# 612_jetracer_328_212.net
KiCad netlist of a schematic drawn in EAGLE
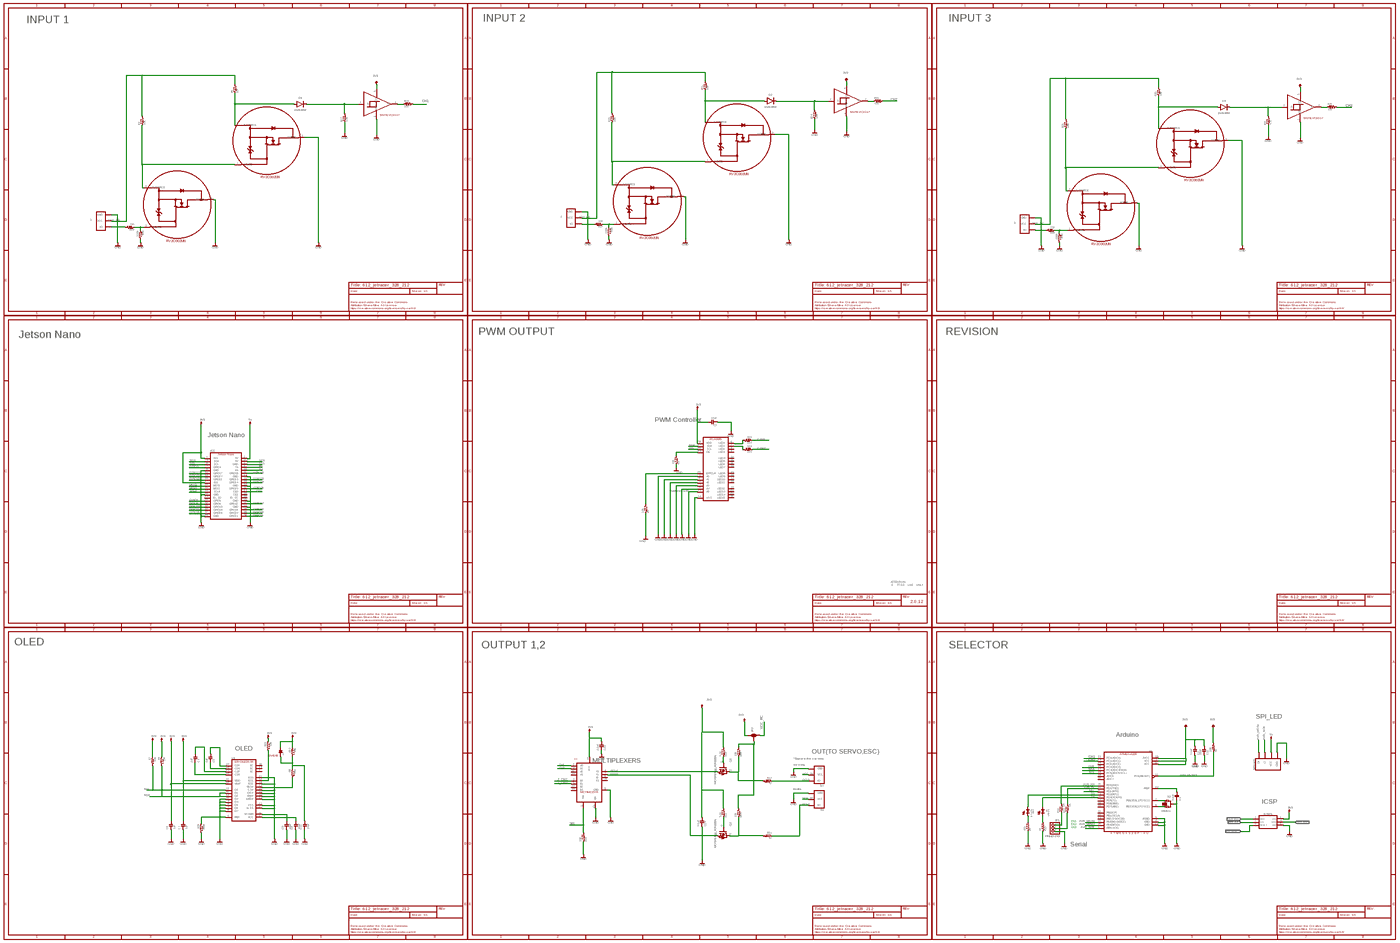
[diagram p0: schematic, sheet 1, overview]
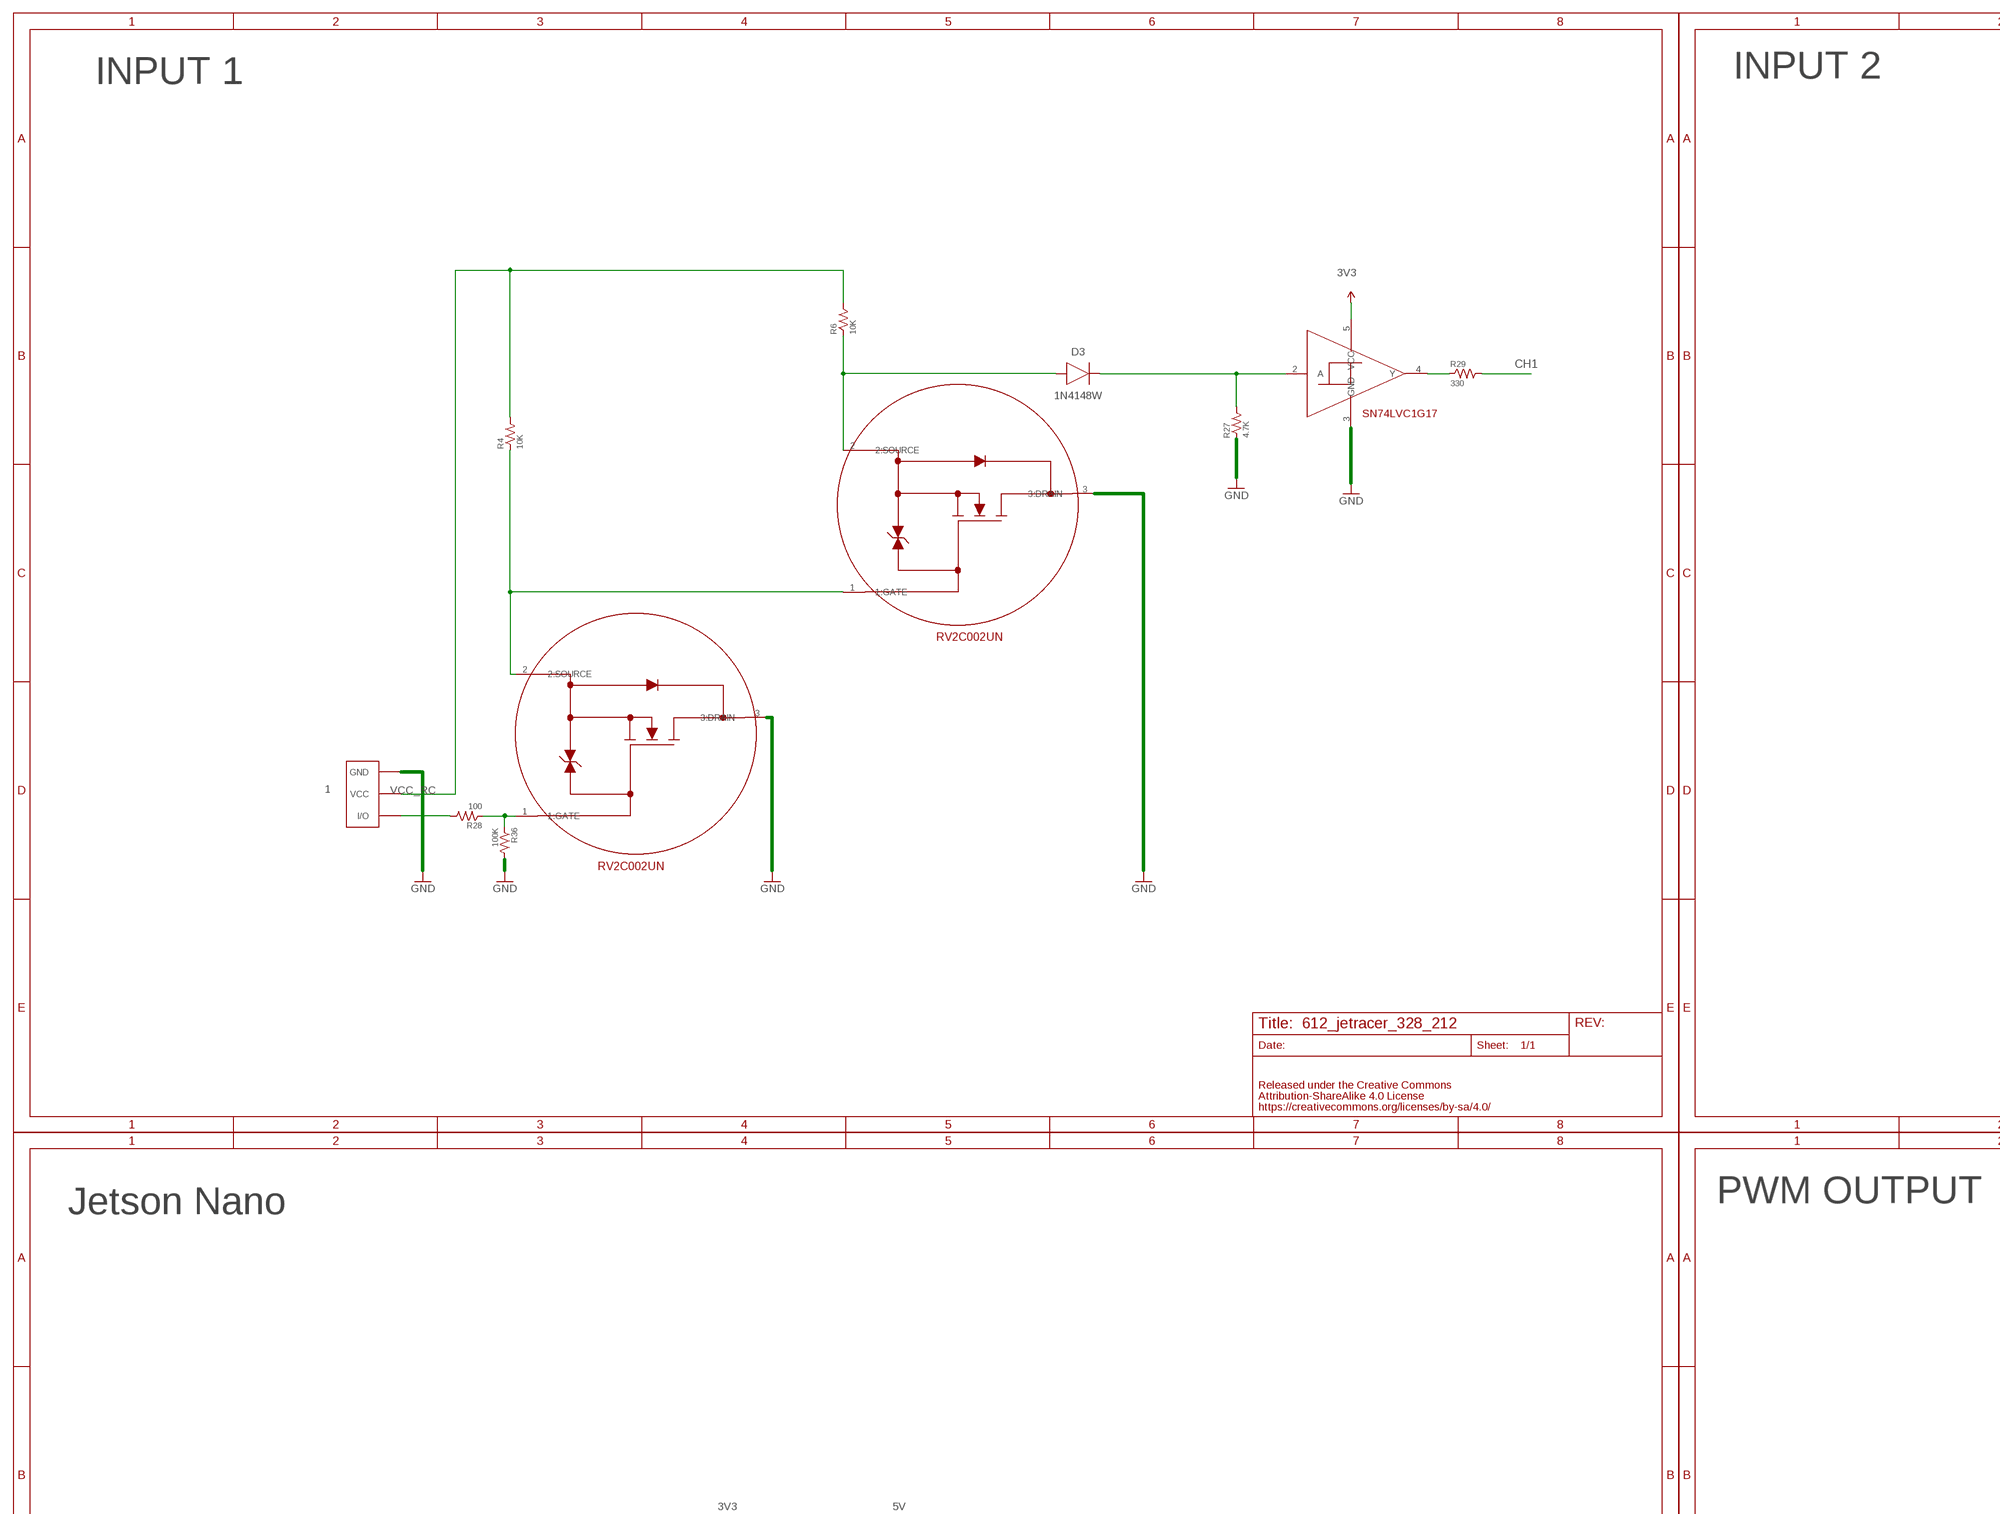
[diagram p1: schematic, sheet 1, part 1 of 6]
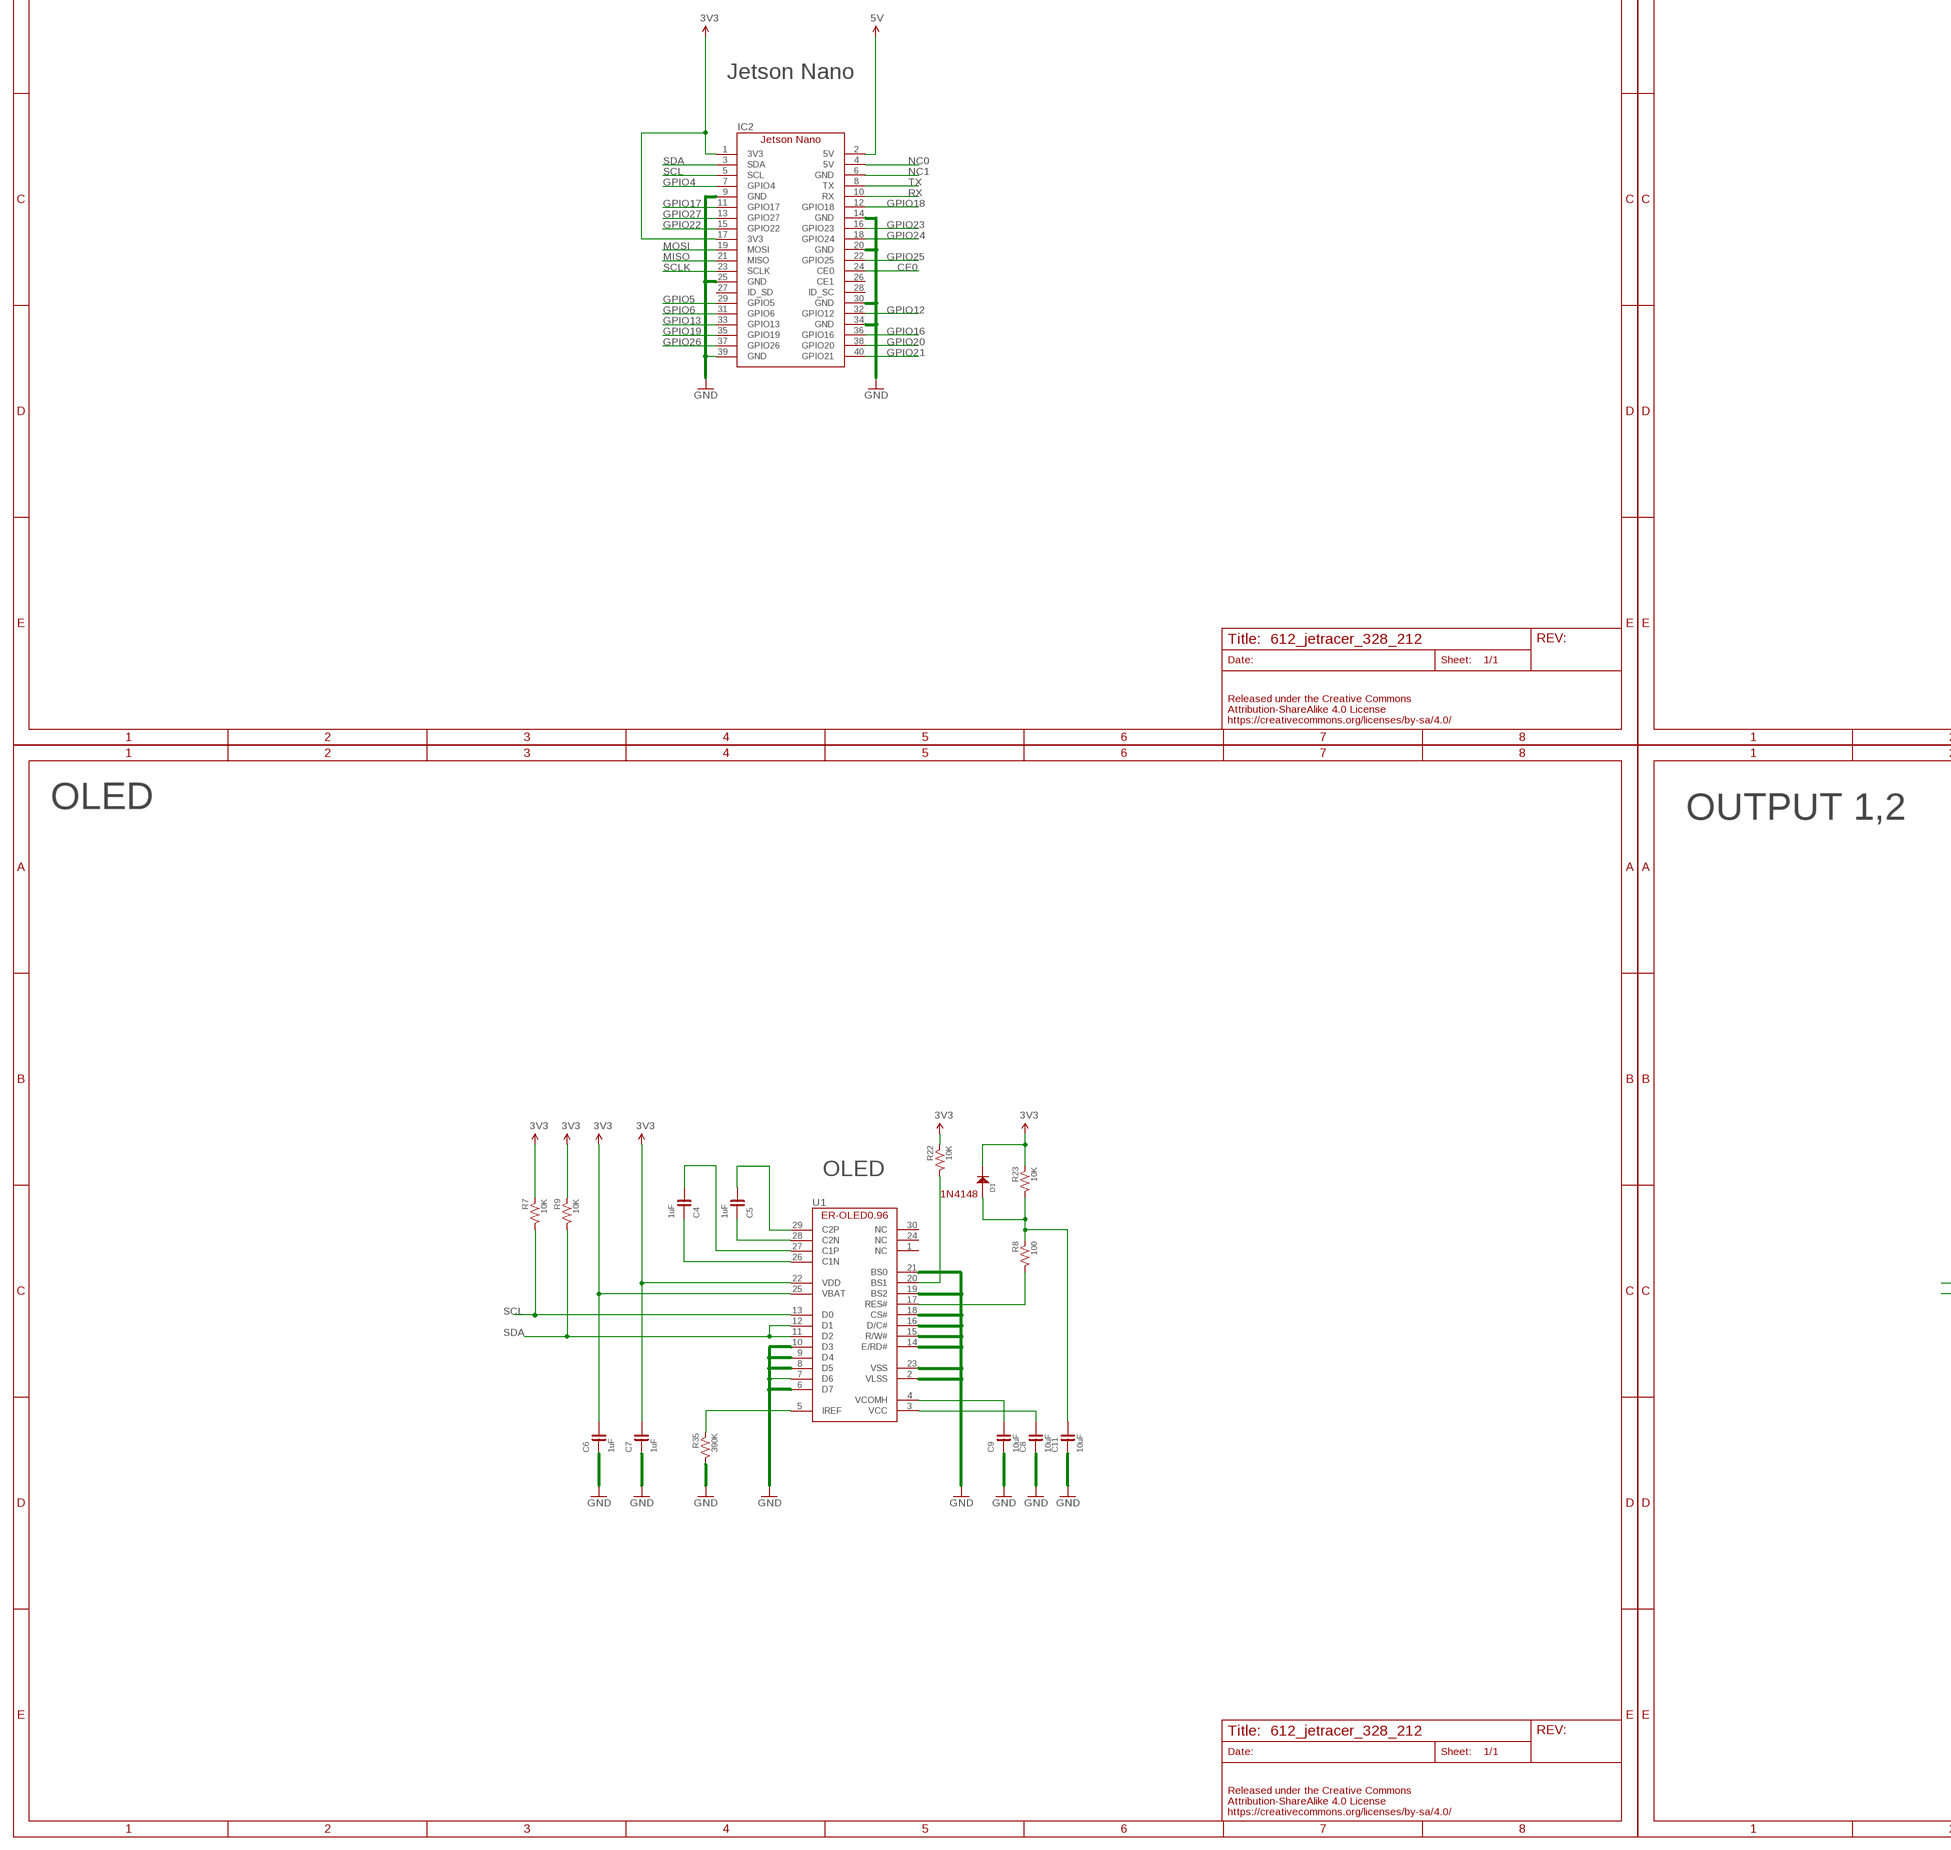
[diagram p2: schematic, sheet 1, part 2 of 6]
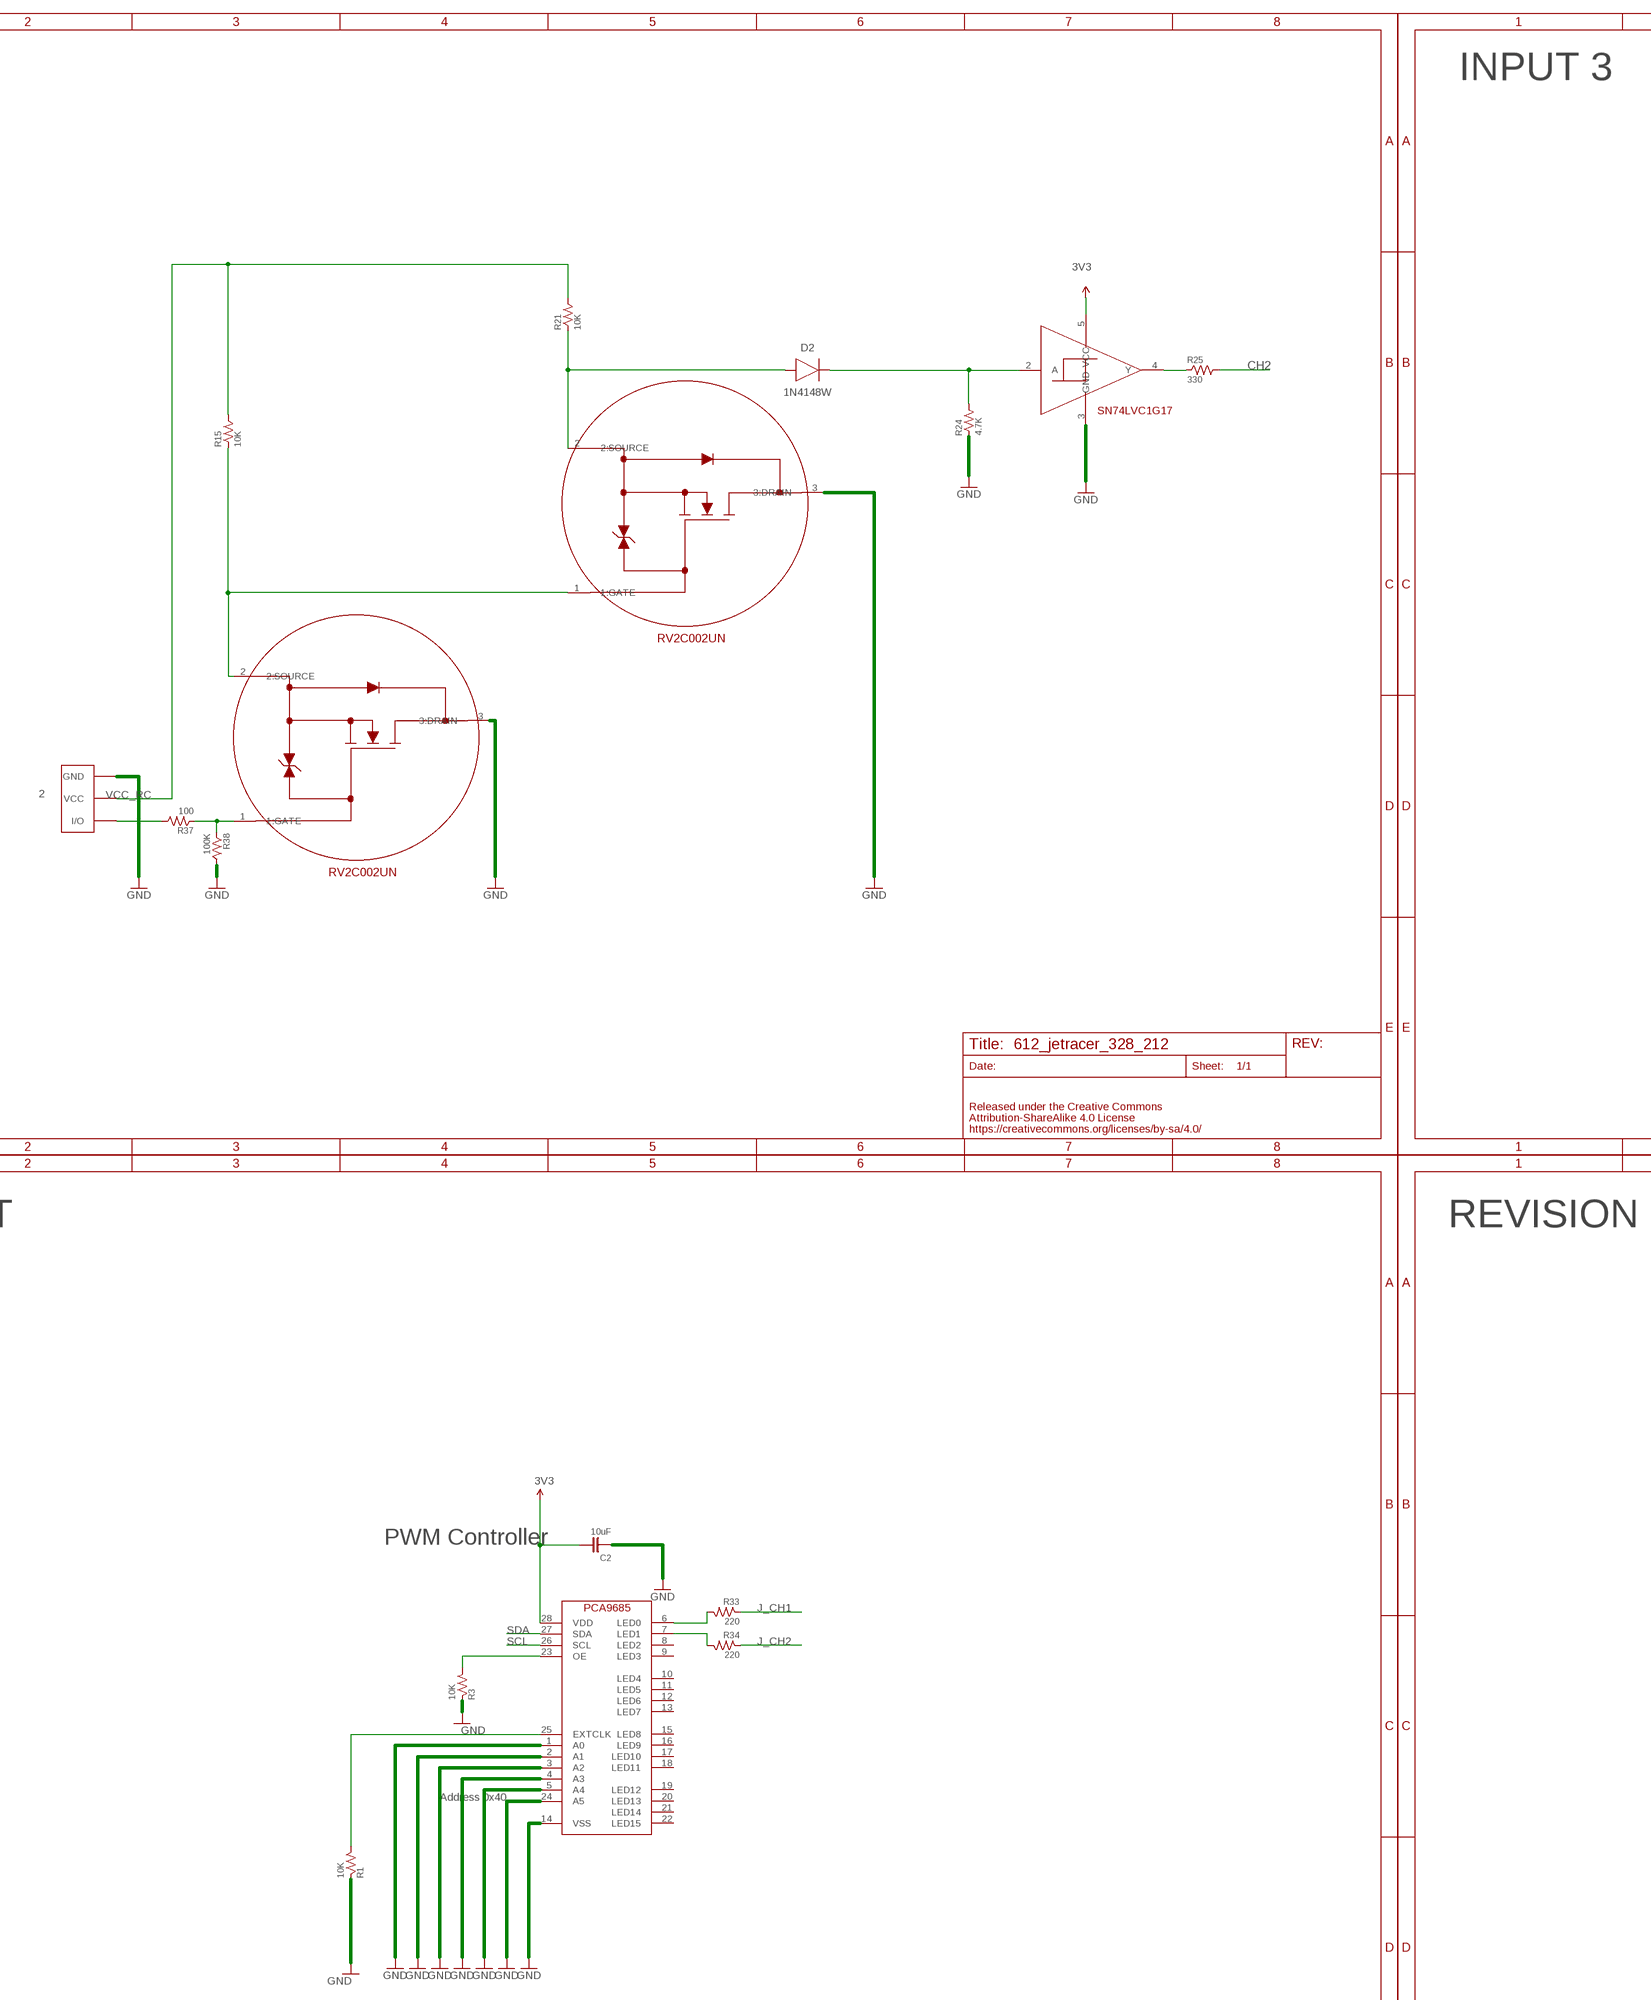
[diagram p3: schematic, sheet 1, part 3 of 6]
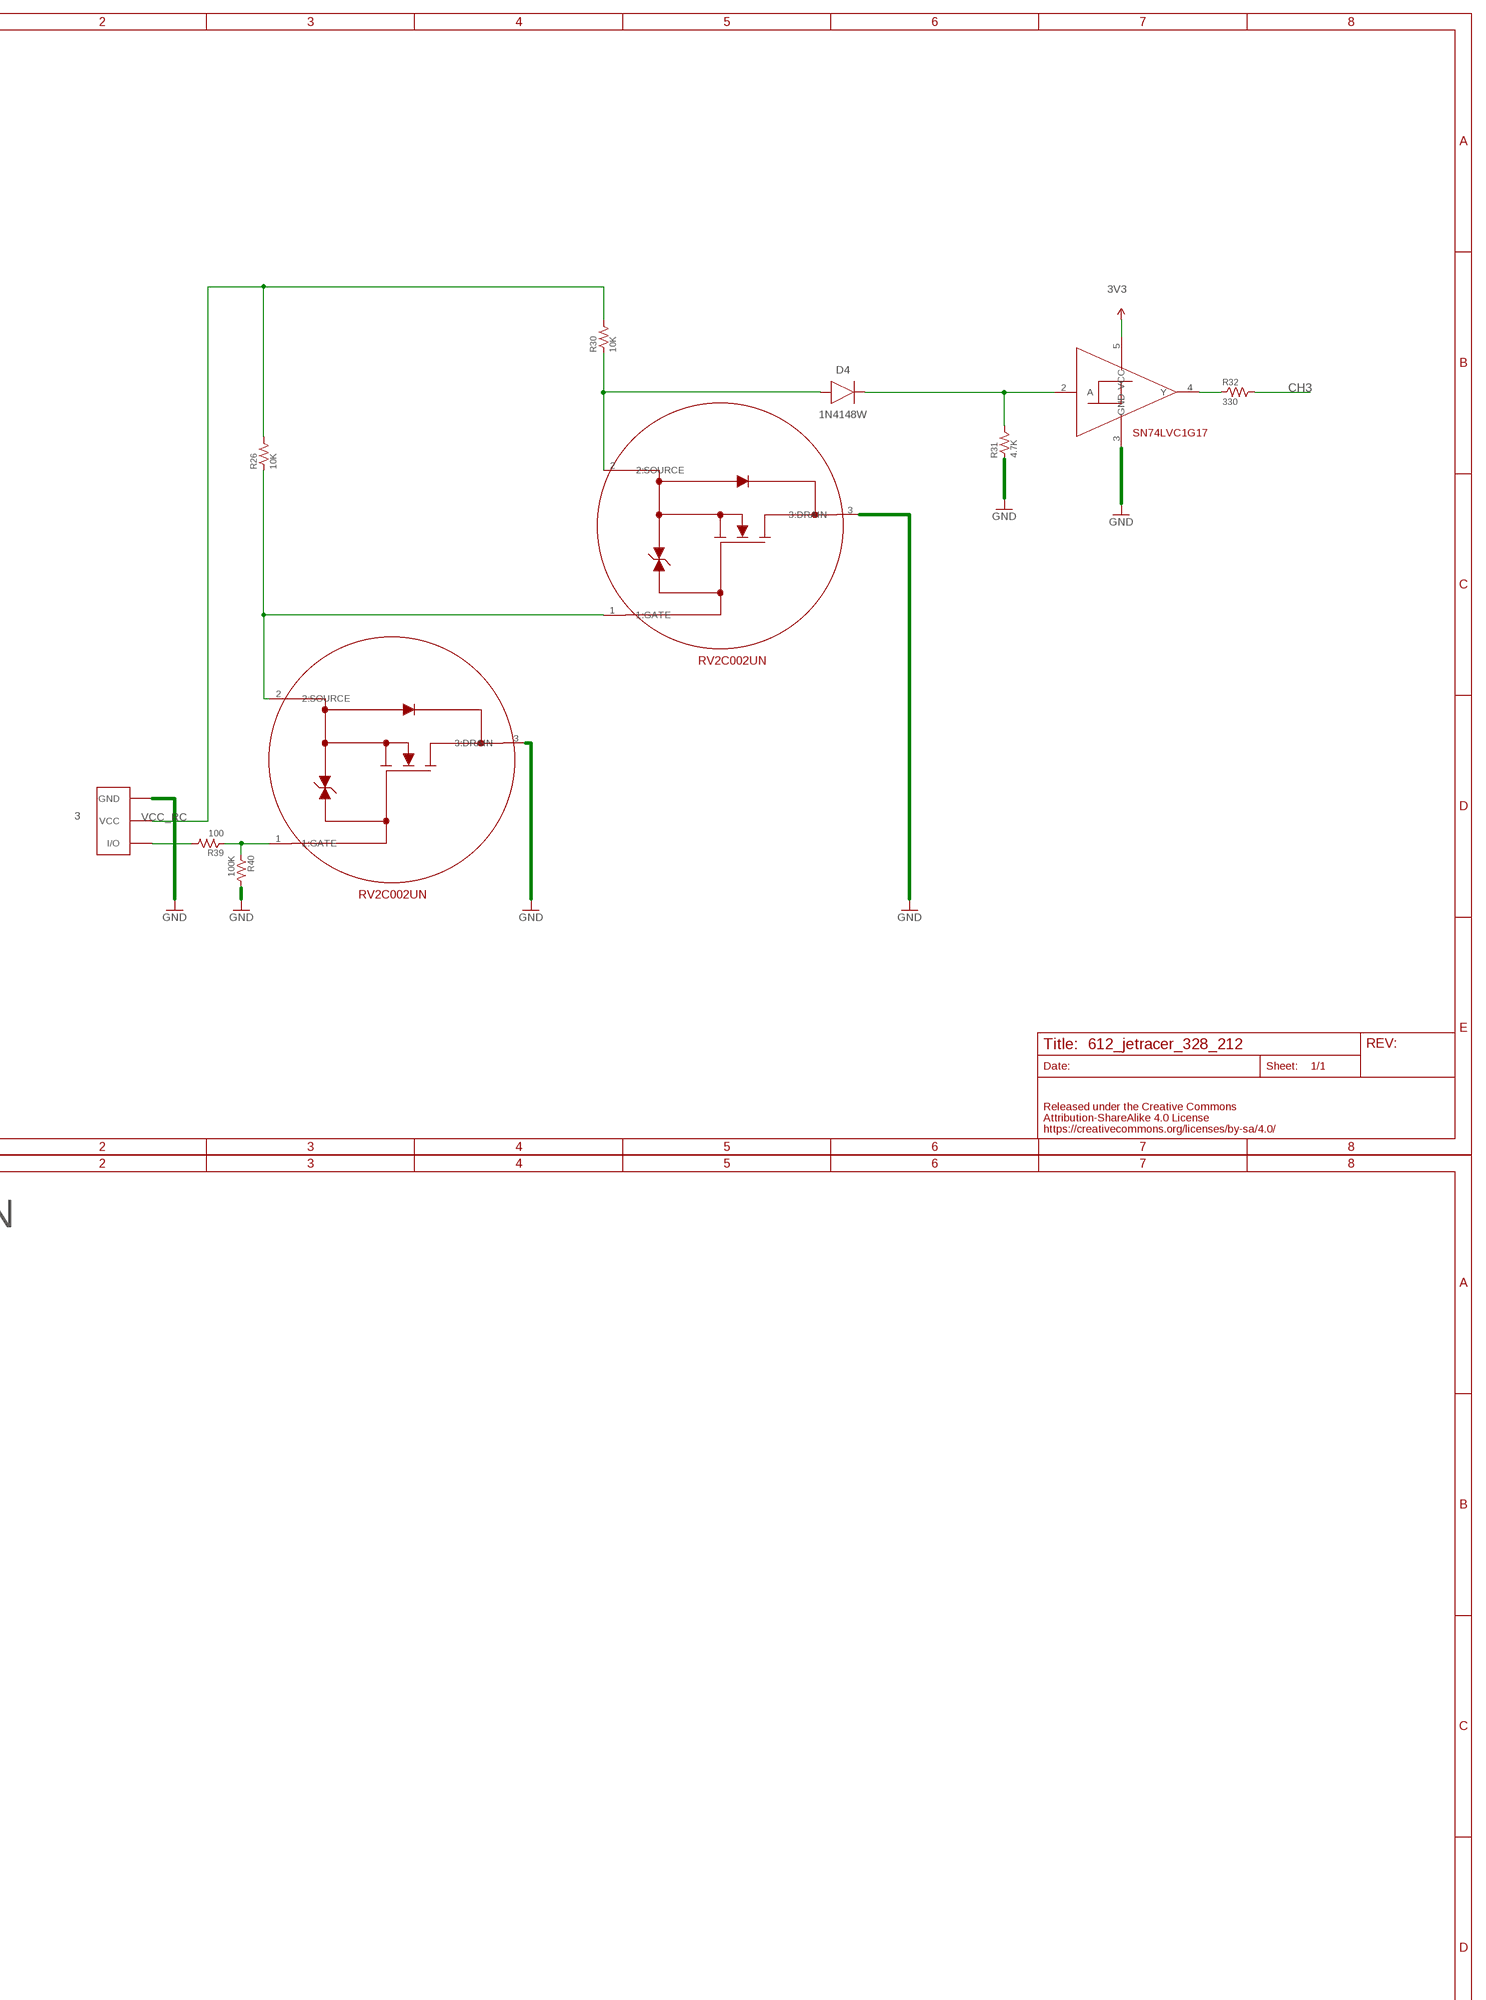
[diagram p4: schematic, sheet 1, part 4 of 6]
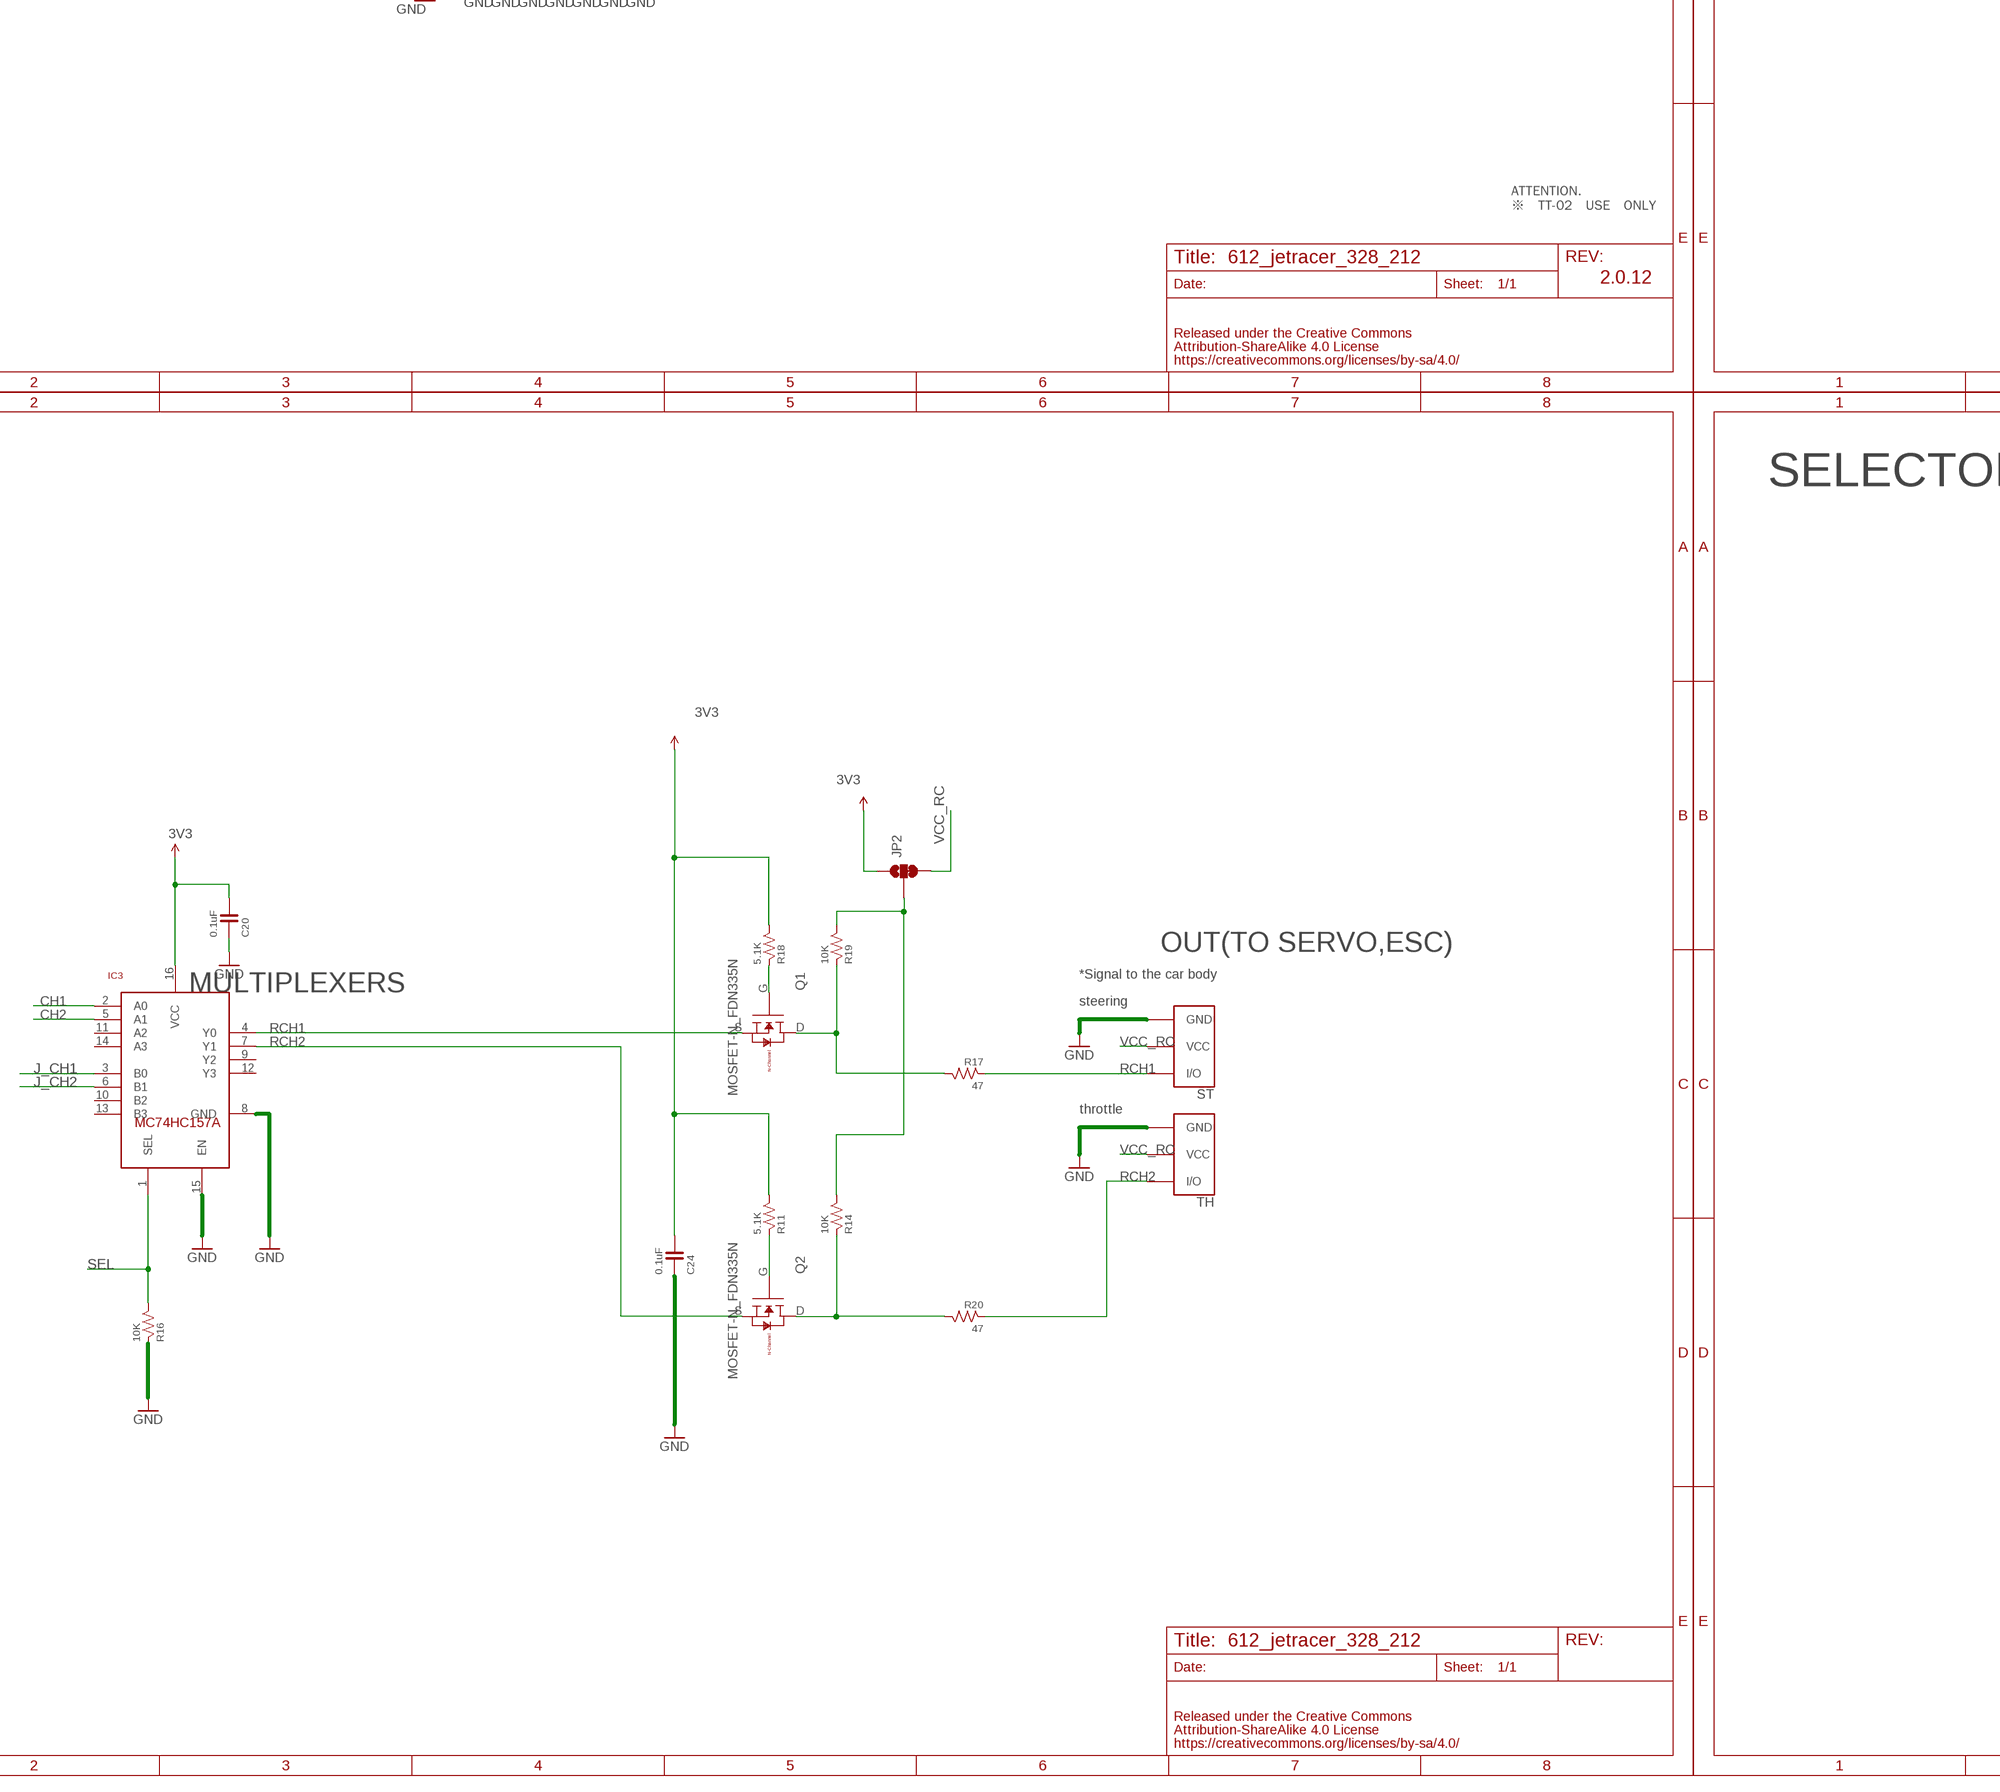
[diagram p5: schematic, sheet 1, part 5 of 6]
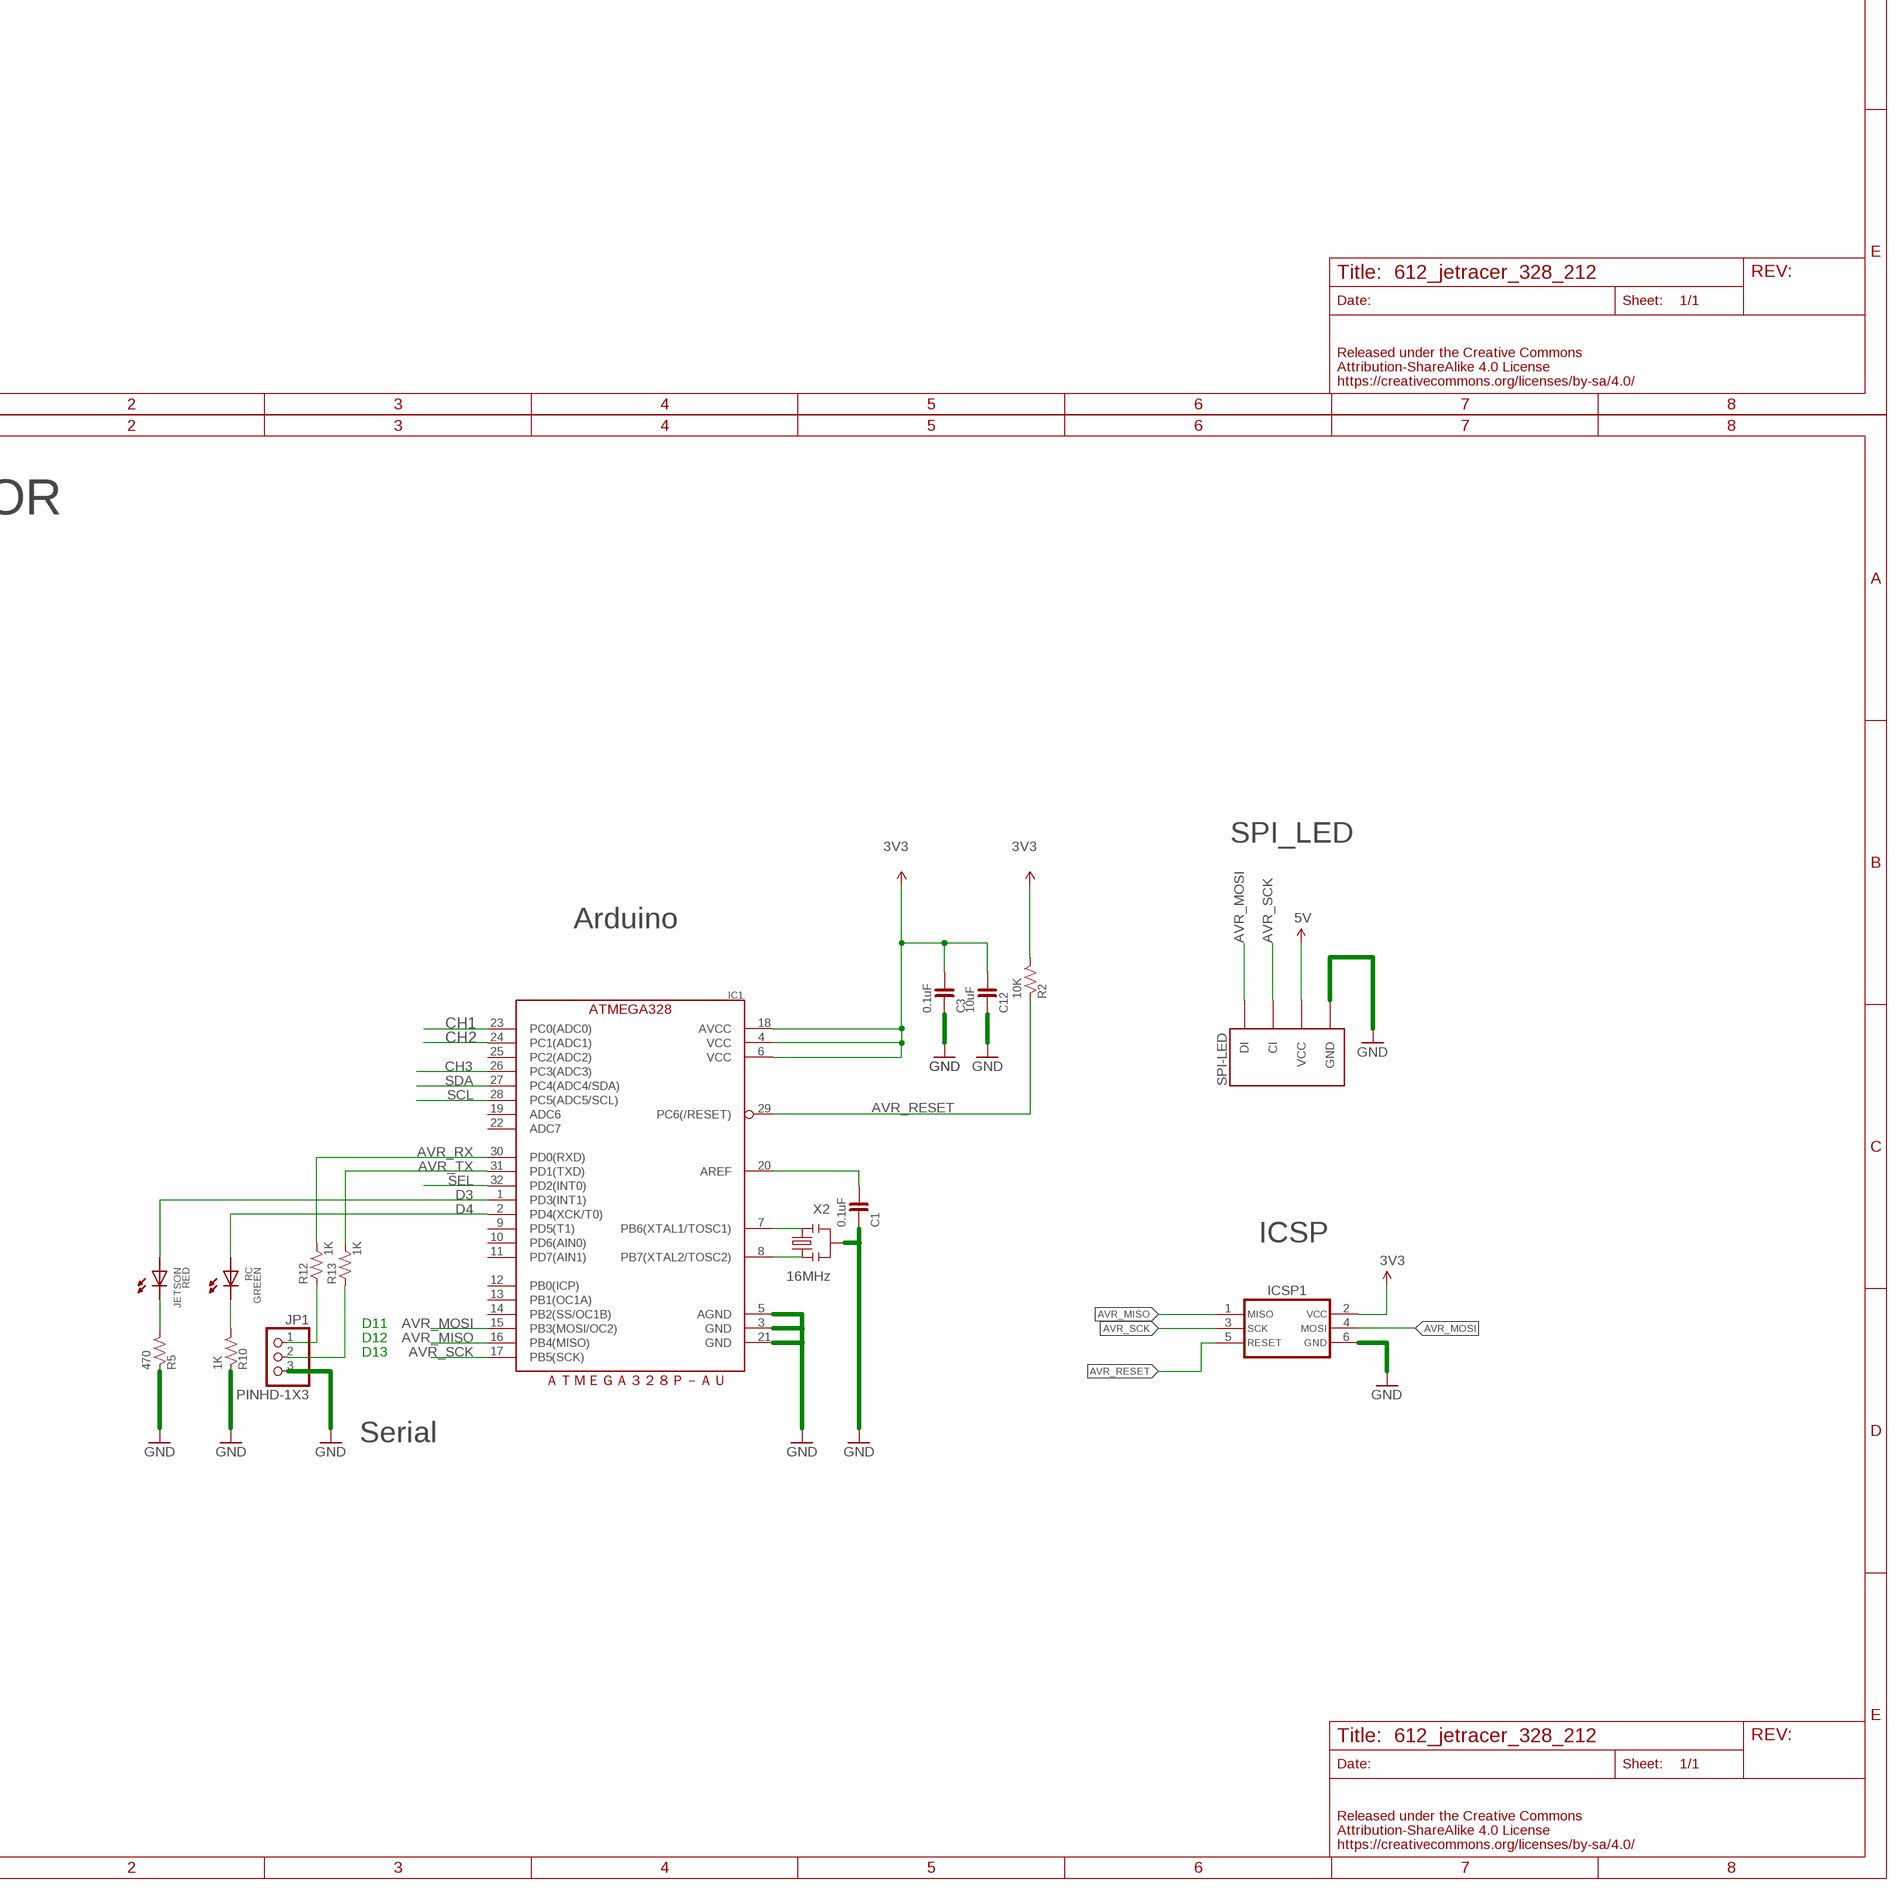
[diagram p6: schematic, sheet 1, part 6 of 6]

(export (version "E")
  (design (tool "Eeschema 10.0.6"))
  (components
    (comp (ref "1")
      (value "FABO_BRICK_3PIN-HEADER")
      (footprint "eagle-import:FABO_BRICK_3PIN_HEADER")
      (libsource (lib "eagle-import") (part "FABO_BRICK_3PIN-HEADER"))
    )
    (comp (ref "2")
      (value "FABO_BRICK_3PIN-HEADER")
      (footprint "eagle-import:FABO_BRICK_3PIN_HEADER")
      (libsource (lib "eagle-import") (part "FABO_BRICK_3PIN-HEADER"))
    )
    (comp (ref "3")
      (value "FABO_BRICK_3PIN-HEADER")
      (footprint "eagle-import:FABO_BRICK_3PIN_HEADER")
      (libsource (lib "eagle-import") (part "FABO_BRICK_3PIN-HEADER"))
    )
    (comp (ref "C1")
      (value "0.1uF")
      (footprint "eagle-import:0603")
      (libsource (lib "eagle-import") (part "CAPACITOR-0603"))
    )
    (comp (ref "C2")
      (value "10uF")
      (footprint "eagle-import:0603")
      (libsource (lib "eagle-import") (part "CAPACITOR-0603"))
    )
    (comp (ref "C3")
      (value "0.1uF")
      (footprint "eagle-import:0603")
      (libsource (lib "eagle-import") (part "CAPACITOR-0603"))
    )
    (comp (ref "C4")
      (value "1uF")
      (footprint "eagle-import:0603")
      (libsource (lib "eagle-import") (part "CAPACITOR-0603"))
    )
    (comp (ref "C5")
      (value "1uF")
      (footprint "eagle-import:0603")
      (libsource (lib "eagle-import") (part "CAPACITOR-0603"))
    )
    (comp (ref "C6")
      (value "1uF")
      (footprint "eagle-import:0603")
      (libsource (lib "eagle-import") (part "CAPACITOR-0603"))
    )
    (comp (ref "C7")
      (value "1uF")
      (footprint "eagle-import:0603")
      (libsource (lib "eagle-import") (part "CAPACITOR-0603"))
    )
    (comp (ref "C8")
      (value "10uF")
      (footprint "eagle-import:0603")
      (libsource (lib "eagle-import") (part "CAPACITOR-0603"))
    )
    (comp (ref "C9")
      (value "10uF")
      (footprint "eagle-import:0603")
      (libsource (lib "eagle-import") (part "CAPACITOR-0603"))
    )
    (comp (ref "C11")
      (value "10uF")
      (footprint "eagle-import:0603")
      (libsource (lib "eagle-import") (part "CAPACITOR-0603"))
    )
    (comp (ref "C12")
      (value "10uF")
      (footprint "eagle-import:0603")
      (libsource (lib "eagle-import") (part "CAPACITOR-0603"))
    )
    (comp (ref "C20")
      (value "0.1uF")
      (footprint "eagle-import:0603")
      (libsource (lib "eagle-import") (part "CAPACITOR-0603"))
    )
    (comp (ref "C24")
      (value "0.1uF")
      (footprint "eagle-import:0603")
      (fields (field (name "SPICEPREFIX") "C"))
      (libsource (lib "eagle-import") (part "CAPACITOR-0603"))
    )
    (comp (ref "D1")
      (value "1N4148")
      (footprint "eagle-import:1N4148W")
      (libsource (lib "eagle-import") (part "1N4148"))
    )
    (comp (ref "D2")
      (value "1N4148W")
      (footprint "eagle-import:SOD3715X135")
      (fields (field (name "MANUFACTURER") "Diodes Incorporated"))
      (libsource (lib "eagle-import") (part "DIODE__SOD123G1N4148W-7-F"))
    )
    (comp (ref "D3")
      (value "1N4148W")
      (footprint "eagle-import:SOD3715X135")
      (fields (field (name "MANUFACTURER") "Diodes Incorporated"))
      (libsource (lib "eagle-import") (part "DIODE__SOD123G1N4148W-7-F"))
    )
    (comp (ref "D4")
      (value "1N4148W")
      (footprint "eagle-import:SOD3715X135")
      (fields (field (name "MANUFACTURER") "Diodes Incorporated"))
      (libsource (lib "eagle-import") (part "DIODE__SOD123G1N4148W-7-F"))
    )
    (comp (ref "IC1")
      (value "ATMEGA328P-AU")
      (footprint "eagle-import:TQFP-32")
      (libsource (lib "eagle-import") (part "ATMEGA328P-AU"))
    )
    (comp (ref "IC2")
      (value "JETSON_NANO_NOBORDER")
      (footprint "eagle-import:JETSON_NANO_NOBOARDER")
      (libsource (lib "eagle-import") (part "JETSON_NANO_NOBORDER"))
    )
    (comp (ref "IC3")
      (value "MULTIPLEXERSMC74HC157A")
      (footprint "eagle-import:TSSOP-16")
      (libsource (lib "eagle-import") (part "MULTIPLEXERSMC74HC157A"))
    )
    (comp (ref "IC4")
      (value "PCA9685")
      (footprint "eagle-import:PCA9685")
      (libsource (lib "eagle-import") (part "PCA9685"))
    )
    (comp (ref "ICSP1")
      (value "ICSP_AVR-TC_NOHOLE")
      (footprint "eagle-import:TC2030")
      (libsource (lib "eagle-import") (part "ICSP_AVR-TC_NOHOLE"))
    )
    (comp (ref "JETSON")
      (value "GREEN")
      (footprint "eagle-import:0603")
      (libsource (lib "eagle-import") (part "LED-0603"))
    )
    (comp (ref "JP1")
      (value "PINHD-1X3")
      (footprint "eagle-import:1X03")
      (libsource (lib "eagle-import") (part "PINHD-1X3"))
    )
    (comp (ref "JP2")
      (value "JUMPER-SMT_3_1-NC_TRACE_SILK")
      (footprint "eagle-import:SMT-JUMPER_3_1-NC_TRACE_SILK")
      (libsource (lib "eagle-import") (part "JUMPER-SMT_3_1-NC_TRACE_SILK"))
    )
    (comp (ref "Q1")
      (value "MOSFET-N_FDN335N")
      (footprint "eagle-import:SUPERSOT-3")
      (libsource (lib "eagle-import") (part "MOSFET-N_FDN335N"))
    )
    (comp (ref "Q2")
      (value "MOSFET-N_FDN335N")
      (footprint "eagle-import:SUPERSOT-3")
      (libsource (lib "eagle-import") (part "MOSFET-N_FDN335N"))
    )
    (comp (ref "R1")
      (value "10K")
      (footprint "eagle-import:0603")
      (libsource (lib "eagle-import") (part "RESISTOR-0603"))
    )
    (comp (ref "R2")
      (value "10K")
      (footprint "eagle-import:0603")
      (libsource (lib "eagle-import") (part "RESISTOR-0603"))
    )
    (comp (ref "R3")
      (value "10K")
      (footprint "eagle-import:0603")
      (libsource (lib "eagle-import") (part "RESISTOR-0603"))
    )
    (comp (ref "R4")
      (value "10K")
      (footprint "eagle-import:0603")
      (libsource (lib "eagle-import") (part "RESISTOR-0603"))
    )
    (comp (ref "R5")
      (value "470")
      (footprint "eagle-import:0603")
      (libsource (lib "eagle-import") (part "RESISTOR-0603"))
    )
    (comp (ref "R6")
      (value "10K")
      (footprint "eagle-import:0603")
      (libsource (lib "eagle-import") (part "RESISTOR-0603"))
    )
    (comp (ref "R7")
      (value "10K")
      (footprint "eagle-import:0603")
      (libsource (lib "eagle-import") (part "RESISTOR-0603"))
    )
    (comp (ref "R8")
      (value "100")
      (footprint "eagle-import:0603")
      (libsource (lib "eagle-import") (part "RESISTOR-0603"))
    )
    (comp (ref "R9")
      (value "10K")
      (footprint "eagle-import:0603")
      (libsource (lib "eagle-import") (part "RESISTOR-0603"))
    )
    (comp (ref "R10")
      (value "1K")
      (footprint "eagle-import:0603")
      (libsource (lib "eagle-import") (part "RESISTOR-0603"))
    )
    (comp (ref "R11")
      (value "5.1K")
      (footprint "eagle-import:0603")
      (libsource (lib "eagle-import") (part "RESISTOR-0603"))
    )
    (comp (ref "R12")
      (value "1K")
      (footprint "eagle-import:0603")
      (libsource (lib "eagle-import") (part "RESISTOR-0603"))
    )
    (comp (ref "R13")
      (value "1K")
      (footprint "eagle-import:0603")
      (libsource (lib "eagle-import") (part "RESISTOR-0603"))
    )
    (comp (ref "R14")
      (value "10K")
      (footprint "eagle-import:0603")
      (libsource (lib "eagle-import") (part "RESISTOR-0603"))
    )
    (comp (ref "R15")
      (value "10K")
      (footprint "eagle-import:0603")
      (libsource (lib "eagle-import") (part "RESISTOR-0603"))
    )
    (comp (ref "R16")
      (value "10K")
      (footprint "eagle-import:0603")
      (libsource (lib "eagle-import") (part "RESISTOR-0603"))
    )
    (comp (ref "R17")
      (value "47")
      (footprint "eagle-import:0603")
      (libsource (lib "eagle-import") (part "RESISTOR-0603"))
    )
    (comp (ref "R18")
      (value "5.1K")
      (footprint "eagle-import:0603")
      (libsource (lib "eagle-import") (part "RESISTOR-0603"))
    )
    (comp (ref "R19")
      (value "10K")
      (footprint "eagle-import:0603")
      (libsource (lib "eagle-import") (part "RESISTOR-0603"))
    )
    (comp (ref "R20")
      (value "47")
      (footprint "eagle-import:0603")
      (libsource (lib "eagle-import") (part "RESISTOR-0603"))
    )
    (comp (ref "R21")
      (value "10K")
      (footprint "eagle-import:0603")
      (libsource (lib "eagle-import") (part "RESISTOR-0603"))
    )
    (comp (ref "R22")
      (value "10K")
      (footprint "eagle-import:0603")
      (libsource (lib "eagle-import") (part "RESISTOR-0603"))
    )
    (comp (ref "R23")
      (value "10K")
      (footprint "eagle-import:0603")
      (libsource (lib "eagle-import") (part "RESISTOR-0603"))
    )
    (comp (ref "R24")
      (value "4.7K")
      (footprint "eagle-import:0603")
      (libsource (lib "eagle-import") (part "RESISTOR-0603"))
    )
    (comp (ref "R25")
      (value "330")
      (footprint "eagle-import:0603")
      (libsource (lib "eagle-import") (part "RESISTOR-0603"))
    )
    (comp (ref "R26")
      (value "10K")
      (footprint "eagle-import:0603")
      (libsource (lib "eagle-import") (part "RESISTOR-0603"))
    )
    (comp (ref "R27")
      (value "4.7K")
      (footprint "eagle-import:0603")
      (libsource (lib "eagle-import") (part "RESISTOR-0603"))
    )
    (comp (ref "R28")
      (value "100")
      (footprint "eagle-import:0603")
      (libsource (lib "eagle-import") (part "RESISTOR-0603"))
    )
    (comp (ref "R29")
      (value "330")
      (footprint "eagle-import:0603")
      (libsource (lib "eagle-import") (part "RESISTOR-0603"))
    )
    (comp (ref "R30")
      (value "10K")
      (footprint "eagle-import:0603")
      (libsource (lib "eagle-import") (part "RESISTOR-0603"))
    )
    (comp (ref "R31")
      (value "4.7K")
      (footprint "eagle-import:0603")
      (libsource (lib "eagle-import") (part "RESISTOR-0603"))
    )
    (comp (ref "R32")
      (value "330")
      (footprint "eagle-import:0603")
      (libsource (lib "eagle-import") (part "RESISTOR-0603"))
    )
    (comp (ref "R33")
      (value "220")
      (footprint "eagle-import:0603")
      (libsource (lib "eagle-import") (part "RESISTOR-0603"))
    )
    (comp (ref "R34")
      (value "220")
      (footprint "eagle-import:0603")
      (libsource (lib "eagle-import") (part "RESISTOR-0603"))
    )
    (comp (ref "R35")
      (value "390K")
      (footprint "eagle-import:0603")
      (libsource (lib "eagle-import") (part "RESISTOR-0603"))
    )
    (comp (ref "R36")
      (value "100K")
      (footprint "eagle-import:0603")
      (libsource (lib "eagle-import") (part "RESISTOR-0603"))
    )
    (comp (ref "R37")
      (value "100")
      (footprint "eagle-import:0603")
      (libsource (lib "eagle-import") (part "RESISTOR-0603"))
    )
    (comp (ref "R38")
      (value "100K")
      (footprint "eagle-import:0603")
      (libsource (lib "eagle-import") (part "RESISTOR-0603"))
    )
    (comp (ref "R39")
      (value "100")
      (footprint "eagle-import:0603")
      (libsource (lib "eagle-import") (part "RESISTOR-0603"))
    )
    (comp (ref "R40")
      (value "100K")
      (footprint "eagle-import:0603")
      (libsource (lib "eagle-import") (part "RESISTOR-0603"))
    )
    (comp (ref "RC")
      (value "RED")
      (footprint "eagle-import:0603")
      (libsource (lib "eagle-import") (part "LED-0603"))
    )
    (comp (ref "SPI-LED")
      (value "FABO-SPI-LED-B04B")
      (footprint "eagle-import:SPI-B04B-PASK-1")
      (libsource (lib "eagle-import") (part "FABO-SPI-LED-B04B"))
    )
    (comp (ref "ST")
      (value "FABO_BRICK_3PIN-HEADER")
      (footprint "eagle-import:FABO_BRICK_3PIN_HEADER")
      (libsource (lib "eagle-import") (part "FABO_BRICK_3PIN-HEADER"))
    )
    (comp (ref "TH")
      (value "FABO_BRICK_3PIN-HEADER")
      (footprint "eagle-import:FABO_BRICK_3PIN_HEADER")
      (libsource (lib "eagle-import") (part "FABO_BRICK_3PIN-HEADER"))
    )
    (comp (ref "U$4")
      (value "RV2C002UN")
      (footprint "eagle-import:DFN1006-3")
      (libsource (lib "eagle-import") (part "RV2C002UN"))
    )
    (comp (ref "U$5")
      (value "RV2C002UN")
      (footprint "eagle-import:DFN1006-3")
      (libsource (lib "eagle-import") (part "RV2C002UN"))
    )
    (comp (ref "U$8")
      (value "RV2C002UN")
      (footprint "eagle-import:DFN1006-3")
      (libsource (lib "eagle-import") (part "RV2C002UN"))
    )
    (comp (ref "U$9")
      (value "RV2C002UN")
      (footprint "eagle-import:DFN1006-3")
      (libsource (lib "eagle-import") (part "RV2C002UN"))
    )
    (comp (ref "U$14")
      (value "SN74LVC1G17")
      (footprint "eagle-import:SOT-23")
      (libsource (lib "eagle-import") (part "SN74LVC1G17"))
    )
    (comp (ref "U$20")
      (value "SN74LVC1G17")
      (footprint "eagle-import:SOT-23")
      (libsource (lib "eagle-import") (part "SN74LVC1G17"))
    )
    (comp (ref "U$21")
      (value "RV2C002UN")
      (footprint "eagle-import:DFN1006-3")
      (libsource (lib "eagle-import") (part "RV2C002UN"))
    )
    (comp (ref "U$22")
      (value "RV2C002UN")
      (footprint "eagle-import:DFN1006-3")
      (libsource (lib "eagle-import") (part "RV2C002UN"))
    )
    (comp (ref "U$23")
      (value "SN74LVC1G17")
      (footprint "eagle-import:SOT-23")
      (libsource (lib "eagle-import") (part "SN74LVC1G17"))
    )
    (comp (ref "U1")
      (value "ER-OLED0.96-1ER-CON30HT-1")
      (footprint "eagle-import:ER-CON30HT-1")
      (libsource (lib "eagle-import") (part "ER-OLED0.96-1ER-CON30HT-1"))
    )
    (comp (ref "X2")
      (value "16MHz")
      (footprint "eagle-import:CSTNE_V_C")
      (libsource (lib "eagle-import") (part "RESONATOR"))
    )
  )
  (nets
    (net (code "1") (name "/AVR_RX") (class "Default")
      (node (ref "IC1") (pin "30") (pinfunction "PD0(RXD)_30") (pintype "bidirectional"))
      (node (ref "R12") (pin "2") (pinfunction "2_2") (pintype "bidirectional"))
    )
    (net (code "2") (name "/AVR_TX") (class "Default")
      (node (ref "IC1") (pin "31") (pinfunction "PD1(TXD)_31") (pintype "bidirectional"))
      (node (ref "R13") (pin "2") (pinfunction "2_2") (pintype "bidirectional"))
    )
    (net (code "3") (name "/CE0") (class "Default")
      (node (ref "IC2") (pin "24") (pinfunction "CE0_24") (pintype "bidirectional"))
    )
    (net (code "4") (name "/CH1") (class "Default")
      (node (ref "IC1") (pin "23") (pinfunction "PC0(ADC0)_23") (pintype "bidirectional"))
      (node (ref "IC3") (pin "2") (pinfunction "A0_2") (pintype "bidirectional"))
      (node (ref "R29") (pin "2") (pinfunction "2_2") (pintype "bidirectional"))
    )
    (net (code "5") (name "/CH2") (class "Default")
      (node (ref "IC1") (pin "24") (pinfunction "PC1(ADC1)_24") (pintype "bidirectional"))
      (node (ref "IC3") (pin "5") (pinfunction "A1_5") (pintype "bidirectional"))
      (node (ref "R25") (pin "2") (pinfunction "2_2") (pintype "bidirectional"))
    )
    (net (code "6") (name "/CH3") (class "Default")
      (node (ref "IC1") (pin "26") (pinfunction "PC3(ADC3)_26") (pintype "bidirectional"))
      (node (ref "R32") (pin "2") (pinfunction "2_2") (pintype "bidirectional"))
    )
    (net (code "7") (name "/D3") (class "Default")
      (node (ref "IC1") (pin "1") (pinfunction "PD3(INT1)_1") (pintype "bidirectional"))
      (node (ref "RC") (pin "ANODE") (pinfunction "ANODE_ANODE") (pintype "passive"))
    )
    (net (code "8") (name "/D4") (class "Default")
      (node (ref "IC1") (pin "2") (pinfunction "PD4(XCK/T0)_2") (pintype "bidirectional"))
      (node (ref "JETSON") (pin "ANODE") (pinfunction "ANODE_ANODE") (pintype "passive"))
    )
    (net (code "9") (name "/GPIO4") (class "Default")
      (node (ref "IC2") (pin "7") (pinfunction "GPIO4_7") (pintype "bidirectional"))
    )
    (net (code "10") (name "/GPIO5") (class "Default")
      (node (ref "IC2") (pin "29") (pinfunction "GPIO5_29") (pintype "bidirectional"))
    )
    (net (code "11") (name "/GPIO6") (class "Default")
      (node (ref "IC2") (pin "31") (pinfunction "GPIO6_31") (pintype "bidirectional"))
    )
    (net (code "12") (name "/GPIO12") (class "Default")
      (node (ref "IC2") (pin "32") (pinfunction "GPIO12_32") (pintype "bidirectional"))
    )
    (net (code "13") (name "/GPIO13") (class "Default")
      (node (ref "IC2") (pin "33") (pinfunction "GPIO13_33") (pintype "bidirectional"))
    )
    (net (code "14") (name "/GPIO16") (class "Default")
      (node (ref "IC2") (pin "36") (pinfunction "GPIO16_36") (pintype "bidirectional"))
    )
    (net (code "15") (name "/GPIO17") (class "Default")
      (node (ref "IC2") (pin "11") (pinfunction "GPIO17_11") (pintype "bidirectional"))
    )
    (net (code "16") (name "/GPIO18") (class "Default")
      (node (ref "IC2") (pin "12") (pinfunction "GPIO18_12") (pintype "bidirectional"))
    )
    (net (code "17") (name "/GPIO19") (class "Default")
      (node (ref "IC2") (pin "35") (pinfunction "GPIO19_35") (pintype "bidirectional"))
    )
    (net (code "18") (name "/GPIO20") (class "Default")
      (node (ref "IC2") (pin "38") (pinfunction "GPIO20_38") (pintype "bidirectional"))
    )
    (net (code "19") (name "/GPIO21") (class "Default")
      (node (ref "IC2") (pin "40") (pinfunction "GPIO21_40") (pintype "bidirectional"))
    )
    (net (code "20") (name "/GPIO22") (class "Default")
      (node (ref "IC2") (pin "15") (pinfunction "GPIO22_15") (pintype "bidirectional"))
    )
    (net (code "21") (name "/GPIO23") (class "Default")
      (node (ref "IC2") (pin "16") (pinfunction "GPIO23_16") (pintype "bidirectional"))
    )
    (net (code "22") (name "/GPIO24") (class "Default")
      (node (ref "IC2") (pin "18") (pinfunction "GPIO24_18") (pintype "bidirectional"))
    )
    (net (code "23") (name "/GPIO25") (class "Default")
      (node (ref "IC2") (pin "22") (pinfunction "GPIO25_22") (pintype "bidirectional"))
    )
    (net (code "24") (name "/GPIO26") (class "Default")
      (node (ref "IC2") (pin "37") (pinfunction "GPIO26_37") (pintype "bidirectional"))
    )
    (net (code "25") (name "/GPIO27") (class "Default")
      (node (ref "IC2") (pin "13") (pinfunction "GPIO27_13") (pintype "bidirectional"))
    )
    (net (code "26") (name "/J_CH1") (class "Default")
      (node (ref "IC3") (pin "3") (pinfunction "B0_3") (pintype "bidirectional"))
      (node (ref "R33") (pin "1") (pinfunction "1_1") (pintype "bidirectional"))
    )
    (net (code "27") (name "/J_CH2") (class "Default")
      (node (ref "IC3") (pin "6") (pinfunction "B1_6") (pintype "bidirectional"))
      (node (ref "R34") (pin "1") (pinfunction "1_1") (pintype "bidirectional"))
    )
    (net (code "28") (name "/MISO") (class "Default")
      (node (ref "IC2") (pin "21") (pinfunction "MISO_21") (pintype "bidirectional"))
    )
    (net (code "29") (name "/MOSI") (class "Default")
      (node (ref "IC2") (pin "19") (pinfunction "MOSI_19") (pintype "bidirectional"))
    )
    (net (code "30") (name "/NC0") (class "Default")
      (node (ref "IC2") (pin "4") (pinfunction "5V_4") (pintype "bidirectional"))
    )
    (net (code "31") (name "/NC1") (class "Default")
      (node (ref "IC2") (pin "6") (pinfunction "GND_6") (pintype "bidirectional"))
    )
    (net (code "32") (name "/RCH1") (class "Default")
      (node (ref "IC3") (pin "4") (pinfunction "Y0_4") (pintype "bidirectional"))
      (node (ref "Q1") (pin "S") (pinfunction "S_S") (pintype "passive"))
    )
    (net (code "33") (name "/RCH2") (class "Default")
      (node (ref "IC3") (pin "7") (pinfunction "Y1_7") (pintype "bidirectional"))
      (node (ref "Q2") (pin "S") (pinfunction "S_S") (pintype "passive"))
    )
    (net (code "34") (name "/RX") (class "Default")
      (node (ref "IC2") (pin "10") (pinfunction "RX_10") (pintype "bidirectional"))
    )
    (net (code "35") (name "/SCL") (class "Default")
      (node (ref "IC1") (pin "28") (pinfunction "PC5(ADC5/SCL)_28") (pintype "bidirectional"))
      (node (ref "IC2") (pin "5") (pinfunction "SCL_5") (pintype "bidirectional"))
      (node (ref "IC4") (pin "26") (pinfunction "SCL_26") (pintype "bidirectional"))
      (node (ref "R7") (pin "2") (pinfunction "2_2") (pintype "bidirectional"))
      (node (ref "U1") (pin "13") (pinfunction "D0_13") (pintype "bidirectional"))
    )
    (net (code "36") (name "/SCLK") (class "Default")
      (node (ref "IC2") (pin "23") (pinfunction "SCLK_23") (pintype "bidirectional"))
    )
    (net (code "37") (name "/SDA") (class "Default")
      (node (ref "IC1") (pin "27") (pinfunction "PC4(ADC4/SDA)_27") (pintype "bidirectional"))
      (node (ref "IC2") (pin "3") (pinfunction "SDA_3") (pintype "bidirectional"))
      (node (ref "IC4") (pin "27") (pinfunction "SDA_27") (pintype "bidirectional"))
      (node (ref "R9") (pin "2") (pinfunction "2_2") (pintype "bidirectional"))
      (node (ref "U1") (pin "11") (pinfunction "D2_11") (pintype "bidirectional"))
      (node (ref "U1") (pin "12") (pinfunction "D1_12") (pintype "bidirectional"))
    )
    (net (code "38") (name "/SEL") (class "Default")
      (node (ref "IC1") (pin "32") (pinfunction "PD2(INT0)_32") (pintype "bidirectional"))
      (node (ref "IC3") (pin "1") (pinfunction "SEL_1") (pintype "bidirectional"))
      (node (ref "R16") (pin "2") (pinfunction "2_2") (pintype "bidirectional"))
    )
    (net (code "39") (name "/TX") (class "Default")
      (node (ref "IC2") (pin "8") (pinfunction "TX_8") (pintype "bidirectional"))
    )
    (net (code "40") (name "/VCC_RC") (class "Default")
      (node (ref "1") (pin "VCC") (pinfunction "VCC_VCC") (pintype "bidirectional"))
      (node (ref "2") (pin "VCC") (pinfunction "VCC_VCC") (pintype "bidirectional"))
      (node (ref "3") (pin "VCC") (pinfunction "VCC_VCC") (pintype "bidirectional"))
      (node (ref "JP2") (pin "3") (pinfunction "3_3") (pintype "passive"))
      (node (ref "R15") (pin "2") (pinfunction "2_2") (pintype "bidirectional"))
      (node (ref "R21") (pin "2") (pinfunction "2_2") (pintype "bidirectional"))
      (node (ref "R26") (pin "2") (pinfunction "2_2") (pintype "bidirectional"))
      (node (ref "R30") (pin "2") (pinfunction "2_2") (pintype "bidirectional"))
      (node (ref "R4") (pin "2") (pinfunction "2_2") (pintype "bidirectional"))
      (node (ref "R6") (pin "2") (pinfunction "2_2") (pintype "bidirectional"))
      (node (ref "ST") (pin "VCC") (pinfunction "VCC_VCC") (pintype "bidirectional"))
      (node (ref "TH") (pin "VCC") (pinfunction "VCC_VCC") (pintype "bidirectional"))
    )
    (net (code "41") (name "3V3") (class "Default")
      (node (ref "C12") (pin "2") (pinfunction "2_2") (pintype "passive"))
      (node (ref "C2") (pin "2") (pinfunction "2_2") (pintype "passive"))
      (node (ref "C20") (pin "2") (pinfunction "2_2") (pintype "passive"))
      (node (ref "C24") (pin "2") (pinfunction "2_2") (pintype "passive"))
      (node (ref "C3") (pin "2") (pinfunction "2_2") (pintype "passive"))
      (node (ref "C6") (pin "2") (pinfunction "2_2") (pintype "passive"))
      (node (ref "C7") (pin "2") (pinfunction "2_2") (pintype "passive"))
      (node (ref "D1") (pin "CATHODE") (pinfunction "CATHODE_CATHODE") (pintype "bidirectional"))
      (node (ref "IC1") (pin "18") (pinfunction "AVCC_18") (pintype "bidirectional"))
      (node (ref "IC1") (pin "4") (pinfunction "VCC_4") (pintype "bidirectional"))
      (node (ref "IC1") (pin "6") (pinfunction "VCC_6") (pintype "bidirectional"))
      (node (ref "IC2") (pin "1") (pinfunction "3V3_1") (pintype "bidirectional"))
      (node (ref "IC2") (pin "17") (pinfunction "3V3_17") (pintype "bidirectional"))
      (node (ref "IC3") (pin "16") (pinfunction "VCC_16") (pintype "bidirectional"))
      (node (ref "IC4") (pin "28") (pinfunction "VDD_28") (pintype "bidirectional"))
      (node (ref "ICSP1") (pin "2") (pinfunction "2_2") (pintype "passive"))
      (node (ref "JP2") (pin "1") (pinfunction "1_1") (pintype "passive"))
      (node (ref "R11") (pin "2") (pinfunction "2_2") (pintype "bidirectional"))
      (node (ref "R18") (pin "2") (pinfunction "2_2") (pintype "bidirectional"))
      (node (ref "R2") (pin "2") (pinfunction "2_2") (pintype "bidirectional"))
      (node (ref "R22") (pin "1") (pinfunction "1_1") (pintype "bidirectional"))
      (node (ref "R23") (pin "1") (pinfunction "1_1") (pintype "bidirectional"))
      (node (ref "R7") (pin "1") (pinfunction "1_1") (pintype "bidirectional"))
      (node (ref "R9") (pin "1") (pinfunction "1_1") (pintype "bidirectional"))
      (node (ref "U$14") (pin "5") (pinfunction "VCC_5") (pintype "bidirectional"))
      (node (ref "U$20") (pin "5") (pinfunction "VCC_5") (pintype "bidirectional"))
      (node (ref "U$23") (pin "5") (pinfunction "VCC_5") (pintype "bidirectional"))
      (node (ref "U1") (pin "22") (pinfunction "VDD_22") (pintype "bidirectional"))
      (node (ref "U1") (pin "25") (pinfunction "VBAT_25") (pintype "bidirectional"))
    )
    (net (code "42") (name "5V") (class "Default")
      (node (ref "IC2") (pin "2") (pinfunction "5V_2") (pintype "bidirectional"))
      (node (ref "SPI-LED") (pin "VCC") (pinfunction "VCC_VCC") (pintype "bidirectional"))
    )
    (net (code "43") (name "AVR_MISO") (class "Default")
      (node (ref "IC1") (pin "16") (pinfunction "PB4(MISO)_16") (pintype "bidirectional"))
      (node (ref "ICSP1") (pin "1") (pinfunction "1_1") (pintype "passive"))
    )
    (net (code "44") (name "AVR_MOSI") (class "Default")
      (node (ref "IC1") (pin "15") (pinfunction "PB3(MOSI/OC2)_15") (pintype "bidirectional"))
      (node (ref "ICSP1") (pin "4") (pinfunction "4_4") (pintype "passive"))
      (node (ref "SPI-LED") (pin "DI") (pinfunction "DI_DI") (pintype "bidirectional"))
    )
    (net (code "45") (name "AVR_RESET") (class "Default")
      (node (ref "IC1") (pin "29") (pinfunction "PC6(/RESET)_29") (pintype "bidirectional"))
      (node (ref "ICSP1") (pin "5") (pinfunction "5_5") (pintype "passive"))
      (node (ref "R2") (pin "1") (pinfunction "1_1") (pintype "bidirectional"))
    )
    (net (code "46") (name "AVR_SCK") (class "Default")
      (node (ref "IC1") (pin "17") (pinfunction "PB5(SCK)_17") (pintype "bidirectional"))
      (node (ref "ICSP1") (pin "3") (pinfunction "3_3") (pintype "passive"))
      (node (ref "SPI-LED") (pin "CI") (pinfunction "CI_CI") (pintype "bidirectional"))
    )
    (net (code "47") (name "GND") (class "Default")
      (node (ref "1") (pin "GND") (pinfunction "GND_GND") (pintype "bidirectional"))
      (node (ref "2") (pin "GND") (pinfunction "GND_GND") (pintype "bidirectional"))
      (node (ref "3") (pin "GND") (pinfunction "GND_GND") (pintype "bidirectional"))
      (node (ref "C1") (pin "1") (pinfunction "1_1") (pintype "passive"))
      (node (ref "C11") (pin "1") (pinfunction "1_1") (pintype "passive"))
      (node (ref "C12") (pin "1") (pinfunction "1_1") (pintype "passive"))
      (node (ref "C2") (pin "1") (pinfunction "1_1") (pintype "passive"))
      (node (ref "C20") (pin "1") (pinfunction "1_1") (pintype "passive"))
      (node (ref "C24") (pin "1") (pinfunction "1_1") (pintype "passive"))
      (node (ref "C3") (pin "1") (pinfunction "1_1") (pintype "passive"))
      (node (ref "C6") (pin "1") (pinfunction "1_1") (pintype "passive"))
      (node (ref "C7") (pin "1") (pinfunction "1_1") (pintype "passive"))
      (node (ref "C8") (pin "1") (pinfunction "1_1") (pintype "passive"))
      (node (ref "C9") (pin "1") (pinfunction "1_1") (pintype "passive"))
      (node (ref "IC1") (pin "21") (pinfunction "GND_21") (pintype "bidirectional"))
      (node (ref "IC1") (pin "3") (pinfunction "GND_3") (pintype "bidirectional"))
      (node (ref "IC1") (pin "5") (pinfunction "AGND_5") (pintype "bidirectional"))
      (node (ref "IC2") (pin "14") (pinfunction "GND_14") (pintype "bidirectional"))
      (node (ref "IC2") (pin "20") (pinfunction "GND_20") (pintype "bidirectional"))
      (node (ref "IC2") (pin "25") (pinfunction "GND_25") (pintype "bidirectional"))
      (node (ref "IC2") (pin "30") (pinfunction "GND_30") (pintype "bidirectional"))
      (node (ref "IC2") (pin "34") (pinfunction "GND_34") (pintype "bidirectional"))
      (node (ref "IC2") (pin "39") (pinfunction "GND_39") (pintype "bidirectional"))
      (node (ref "IC2") (pin "9") (pinfunction "GND_9") (pintype "bidirectional"))
      (node (ref "IC3") (pin "15") (pinfunction "EN_15") (pintype "bidirectional"))
      (node (ref "IC3") (pin "8") (pinfunction "GND_8") (pintype "bidirectional"))
      (node (ref "IC4") (pin "1") (pinfunction "A0_1") (pintype "bidirectional"))
      (node (ref "IC4") (pin "14") (pinfunction "VSS_14") (pintype "bidirectional"))
      (node (ref "IC4") (pin "2") (pinfunction "A1_2") (pintype "bidirectional"))
      (node (ref "IC4") (pin "24") (pinfunction "A5_24") (pintype "bidirectional"))
      (node (ref "IC4") (pin "3") (pinfunction "A2_3") (pintype "bidirectional"))
      (node (ref "IC4") (pin "4") (pinfunction "A3_4") (pintype "bidirectional"))
      (node (ref "IC4") (pin "5") (pinfunction "A4_5") (pintype "bidirectional"))
      (node (ref "ICSP1") (pin "6") (pinfunction "6_6") (pintype "passive"))
      (node (ref "JP1") (pin "3") (pinfunction "3_3") (pintype "passive"))
      (node (ref "R1") (pin "1") (pinfunction "1_1") (pintype "bidirectional"))
      (node (ref "R10") (pin "1") (pinfunction "1_1") (pintype "bidirectional"))
      (node (ref "R16") (pin "1") (pinfunction "1_1") (pintype "bidirectional"))
      (node (ref "R24") (pin "1") (pinfunction "1_1") (pintype "bidirectional"))
      (node (ref "R27") (pin "1") (pinfunction "1_1") (pintype "bidirectional"))
      (node (ref "R3") (pin "1") (pinfunction "1_1") (pintype "bidirectional"))
      (node (ref "R31") (pin "1") (pinfunction "1_1") (pintype "bidirectional"))
      (node (ref "R35") (pin "2") (pinfunction "2_2") (pintype "bidirectional"))
      (node (ref "R36") (pin "2") (pinfunction "2_2") (pintype "bidirectional"))
      (node (ref "R38") (pin "2") (pinfunction "2_2") (pintype "bidirectional"))
      (node (ref "R40") (pin "2") (pinfunction "2_2") (pintype "bidirectional"))
      (node (ref "R5") (pin "1") (pinfunction "1_1") (pintype "bidirectional"))
      (node (ref "SPI-LED") (pin "GND") (pinfunction "GND_GND") (pintype "bidirectional"))
      (node (ref "ST") (pin "GND") (pinfunction "GND_GND") (pintype "bidirectional"))
      (node (ref "TH") (pin "GND") (pinfunction "GND_GND") (pintype "bidirectional"))
      (node (ref "U$14") (pin "3") (pinfunction "GND_3") (pintype "bidirectional"))
      (node (ref "U$20") (pin "3") (pinfunction "GND_3") (pintype "bidirectional"))
      (node (ref "U$21") (pin "3") (pinfunction "3:DRAIN_3") (pintype "bidirectional"))
      (node (ref "U$22") (pin "3") (pinfunction "3:DRAIN_3") (pintype "bidirectional"))
      (node (ref "U$23") (pin "3") (pinfunction "GND_3") (pintype "bidirectional"))
      (node (ref "U$4") (pin "3") (pinfunction "3:DRAIN_3") (pintype "bidirectional"))
      (node (ref "U$5") (pin "3") (pinfunction "3:DRAIN_3") (pintype "bidirectional"))
      (node (ref "U$8") (pin "3") (pinfunction "3:DRAIN_3") (pintype "bidirectional"))
      (node (ref "U$9") (pin "3") (pinfunction "3:DRAIN_3") (pintype "bidirectional"))
      (node (ref "U1") (pin "10") (pinfunction "D3_10") (pintype "bidirectional"))
      (node (ref "U1") (pin "14") (pinfunction "E/RD#_14") (pintype "bidirectional"))
      (node (ref "U1") (pin "15") (pinfunction "R/W#_15") (pintype "bidirectional"))
      (node (ref "U1") (pin "16") (pinfunction "D/C#_16") (pintype "bidirectional"))
      (node (ref "U1") (pin "18") (pinfunction "CS#_18") (pintype "bidirectional"))
      (node (ref "U1") (pin "19") (pinfunction "BS2_19") (pintype "bidirectional"))
      (node (ref "U1") (pin "2") (pinfunction "VLSS_2") (pintype "bidirectional"))
      (node (ref "U1") (pin "21") (pinfunction "BS0_21") (pintype "bidirectional"))
      (node (ref "U1") (pin "23") (pinfunction "VSS_23") (pintype "bidirectional"))
      (node (ref "U1") (pin "6") (pinfunction "D7_6") (pintype "bidirectional"))
      (node (ref "U1") (pin "7") (pinfunction "D6_7") (pintype "bidirectional"))
      (node (ref "U1") (pin "8") (pinfunction "D5_8") (pintype "bidirectional"))
      (node (ref "U1") (pin "9") (pinfunction "D4_9") (pintype "bidirectional"))
      (node (ref "X2") (pin "2") (pinfunction "2_2") (pintype "passive"))
    )
    (net (code "48") (name "Net-(1-PadI{slash}O)") (class "Default")
      (node (ref "1") (pin "I/O") (pinfunction "I/O_I/O") (pintype "bidirectional"))
      (node (ref "R28") (pin "2") (pinfunction "2_2") (pintype "bidirectional"))
    )
    (net (code "49") (name "Net-(2-PadI{slash}O)") (class "Default")
      (node (ref "2") (pin "I/O") (pinfunction "I/O_I/O") (pintype "bidirectional"))
      (node (ref "R37") (pin "2") (pinfunction "2_2") (pintype "bidirectional"))
    )
    (net (code "50") (name "Net-(3-PadI{slash}O)") (class "Default")
      (node (ref "3") (pin "I/O") (pinfunction "I/O_I/O") (pintype "bidirectional"))
      (node (ref "R39") (pin "2") (pinfunction "2_2") (pintype "bidirectional"))
    )
    (net (code "51") (name "Net-(C11-Pad2)") (class "Default")
      (node (ref "C11") (pin "2") (pinfunction "2_2") (pintype "passive"))
      (node (ref "D1") (pin "ANODE") (pinfunction "ANODE_ANODE") (pintype "bidirectional"))
      (node (ref "R23") (pin "2") (pinfunction "2_2") (pintype "bidirectional"))
      (node (ref "R8") (pin "1") (pinfunction "1_1") (pintype "bidirectional"))
    )
    (net (code "52") (name "Net-(D2-A)") (class "Default")
      (node (ref "D2") (pin "2") (pinfunction "A_2") (pintype "passive"))
      (node (ref "R21") (pin "1") (pinfunction "1_1") (pintype "bidirectional"))
      (node (ref "U$9") (pin "2") (pinfunction "2:SOURCE_2") (pintype "bidirectional"))
    )
    (net (code "53") (name "Net-(D2-C)") (class "Default")
      (node (ref "D2") (pin "1") (pinfunction "C_1") (pintype "passive"))
      (node (ref "R24") (pin "2") (pinfunction "2_2") (pintype "bidirectional"))
      (node (ref "U$20") (pin "2") (pinfunction "A_2") (pintype "bidirectional"))
    )
    (net (code "54") (name "Net-(D3-A)") (class "Default")
      (node (ref "D3") (pin "2") (pinfunction "A_2") (pintype "passive"))
      (node (ref "R6") (pin "1") (pinfunction "1_1") (pintype "bidirectional"))
      (node (ref "U$5") (pin "2") (pinfunction "2:SOURCE_2") (pintype "bidirectional"))
    )
    (net (code "55") (name "Net-(D3-C)") (class "Default")
      (node (ref "D3") (pin "1") (pinfunction "C_1") (pintype "passive"))
      (node (ref "R27") (pin "2") (pinfunction "2_2") (pintype "bidirectional"))
      (node (ref "U$14") (pin "2") (pinfunction "A_2") (pintype "bidirectional"))
    )
    (net (code "56") (name "Net-(D4-A)") (class "Default")
      (node (ref "D4") (pin "2") (pinfunction "A_2") (pintype "passive"))
      (node (ref "R30") (pin "1") (pinfunction "1_1") (pintype "bidirectional"))
      (node (ref "U$22") (pin "2") (pinfunction "2:SOURCE_2") (pintype "bidirectional"))
    )
    (net (code "57") (name "Net-(D4-C)") (class "Default")
      (node (ref "D4") (pin "1") (pinfunction "C_1") (pintype "passive"))
      (node (ref "R31") (pin "2") (pinfunction "2_2") (pintype "bidirectional"))
      (node (ref "U$23") (pin "2") (pinfunction "A_2") (pintype "bidirectional"))
    )
    (net (code "58") (name "Net-(IC1-AREF)") (class "Default")
      (node (ref "C1") (pin "2") (pinfunction "2_2") (pintype "passive"))
      (node (ref "IC1") (pin "20") (pinfunction "AREF_20") (pintype "bidirectional"))
    )
    (net (code "59") (name "Net-(IC1-PB6(XTAL1{slash}TOSC1))") (class "Default")
      (node (ref "IC1") (pin "7") (pinfunction "PB6(XTAL1/TOSC1)_7") (pintype "bidirectional"))
      (node (ref "X2") (pin "1") (pinfunction "1_1") (pintype "passive"))
    )
    (net (code "60") (name "Net-(IC1-PB7(XTAL2{slash}TOSC2))") (class "Default")
      (node (ref "IC1") (pin "8") (pinfunction "PB7(XTAL2/TOSC2)_8") (pintype "bidirectional"))
      (node (ref "X2") (pin "3") (pinfunction "3_3") (pintype "passive"))
    )
    (net (code "61") (name "Net-(IC4-EXTCLK)") (class "Default")
      (node (ref "IC4") (pin "25") (pinfunction "EXTCLK_25") (pintype "bidirectional"))
      (node (ref "R1") (pin "2") (pinfunction "2_2") (pintype "bidirectional"))
    )
    (net (code "62") (name "Net-(IC4-LED0)") (class "Default")
      (node (ref "IC4") (pin "6") (pinfunction "LED0_6") (pintype "bidirectional"))
      (node (ref "R33") (pin "2") (pinfunction "2_2") (pintype "bidirectional"))
    )
    (net (code "63") (name "Net-(IC4-LED1)") (class "Default")
      (node (ref "IC4") (pin "7") (pinfunction "LED1_7") (pintype "bidirectional"))
      (node (ref "R34") (pin "2") (pinfunction "2_2") (pintype "bidirectional"))
    )
    (net (code "64") (name "Net-(IC4-OE)") (class "Default")
      (node (ref "IC4") (pin "23") (pinfunction "OE_23") (pintype "bidirectional"))
      (node (ref "R3") (pin "2") (pinfunction "2_2") (pintype "bidirectional"))
    )
    (net (code "65") (name "Net-(JETSON-PadCATHODE)") (class "Default")
      (node (ref "JETSON") (pin "CATHODE") (pinfunction "CATHODE_CATHODE") (pintype "passive"))
      (node (ref "R10") (pin "2") (pinfunction "2_2") (pintype "bidirectional"))
    )
    (net (code "66") (name "Net-(JP1-Pad1)") (class "Default")
      (node (ref "JP1") (pin "1") (pinfunction "1_1") (pintype "passive"))
      (node (ref "R12") (pin "1") (pinfunction "1_1") (pintype "bidirectional"))
    )
    (net (code "67") (name "Net-(JP1-Pad2)") (class "Default")
      (node (ref "JP1") (pin "2") (pinfunction "2_2") (pintype "passive"))
      (node (ref "R13") (pin "1") (pinfunction "1_1") (pintype "bidirectional"))
    )
    (net (code "68") (name "Net-(JP2-Pad2)") (class "Default")
      (node (ref "JP2") (pin "2") (pinfunction "2_2") (pintype "passive"))
      (node (ref "R14") (pin "2") (pinfunction "2_2") (pintype "bidirectional"))
      (node (ref "R19") (pin "2") (pinfunction "2_2") (pintype "bidirectional"))
    )
    (net (code "69") (name "Net-(Q1-PadD)") (class "Default")
      (node (ref "Q1") (pin "D") (pinfunction "D_D") (pintype "passive"))
      (node (ref "R17") (pin "2") (pinfunction "2_2") (pintype "bidirectional"))
      (node (ref "R19") (pin "1") (pinfunction "1_1") (pintype "bidirectional"))
    )
    (net (code "70") (name "Net-(Q1-PadG)") (class "Default")
      (node (ref "Q1") (pin "G") (pinfunction "G_G") (pintype "passive"))
      (node (ref "R18") (pin "1") (pinfunction "1_1") (pintype "bidirectional"))
    )
    (net (code "71") (name "Net-(Q2-PadD)") (class "Default")
      (node (ref "Q2") (pin "D") (pinfunction "D_D") (pintype "passive"))
      (node (ref "R14") (pin "1") (pinfunction "1_1") (pintype "bidirectional"))
      (node (ref "R20") (pin "2") (pinfunction "2_2") (pintype "bidirectional"))
    )
    (net (code "72") (name "Net-(Q2-PadG)") (class "Default")
      (node (ref "Q2") (pin "G") (pinfunction "G_G") (pintype "passive"))
      (node (ref "R11") (pin "1") (pinfunction "1_1") (pintype "bidirectional"))
    )
    (net (code "73") (name "Net-(R5-Pad2)") (class "Default")
      (node (ref "R5") (pin "2") (pinfunction "2_2") (pintype "bidirectional"))
      (node (ref "RC") (pin "CATHODE") (pinfunction "CATHODE_CATHODE") (pintype "passive"))
    )
    (net (code "74") (name "Net-(R17-Pad1)") (class "Default")
      (node (ref "R17") (pin "1") (pinfunction "1_1") (pintype "bidirectional"))
      (node (ref "ST") (pin "I/O") (pinfunction "I/O_I/O") (pintype "bidirectional"))
    )
    (net (code "75") (name "Net-(R20-Pad1)") (class "Default")
      (node (ref "R20") (pin "1") (pinfunction "1_1") (pintype "bidirectional"))
      (node (ref "TH") (pin "I/O") (pinfunction "I/O_I/O") (pintype "bidirectional"))
    )
    (net (code "76") (name "Net-(U$4-1:GATE)") (class "Default")
      (node (ref "R28") (pin "1") (pinfunction "1_1") (pintype "bidirectional"))
      (node (ref "R36") (pin "1") (pinfunction "1_1") (pintype "bidirectional"))
      (node (ref "U$4") (pin "1") (pinfunction "1:GATE_1") (pintype "bidirectional"))
    )
    (net (code "77") (name "Net-(U$4-2:SOURCE)") (class "Default")
      (node (ref "R4") (pin "1") (pinfunction "1_1") (pintype "bidirectional"))
      (node (ref "U$4") (pin "2") (pinfunction "2:SOURCE_2") (pintype "bidirectional"))
      (node (ref "U$5") (pin "1") (pinfunction "1:GATE_1") (pintype "bidirectional"))
    )
    (net (code "78") (name "Net-(U$8-1:GATE)") (class "Default")
      (node (ref "R37") (pin "1") (pinfunction "1_1") (pintype "bidirectional"))
      (node (ref "R38") (pin "1") (pinfunction "1_1") (pintype "bidirectional"))
      (node (ref "U$8") (pin "1") (pinfunction "1:GATE_1") (pintype "bidirectional"))
    )
    (net (code "79") (name "Net-(U$8-2:SOURCE)") (class "Default")
      (node (ref "R15") (pin "1") (pinfunction "1_1") (pintype "bidirectional"))
      (node (ref "U$8") (pin "2") (pinfunction "2:SOURCE_2") (pintype "bidirectional"))
      (node (ref "U$9") (pin "1") (pinfunction "1:GATE_1") (pintype "bidirectional"))
    )
    (net (code "80") (name "Net-(U$14-Y)") (class "Default")
      (node (ref "R29") (pin "1") (pinfunction "1_1") (pintype "bidirectional"))
      (node (ref "U$14") (pin "4") (pinfunction "Y_4") (pintype "bidirectional"))
    )
    (net (code "81") (name "Net-(U$20-Y)") (class "Default")
      (node (ref "R25") (pin "1") (pinfunction "1_1") (pintype "bidirectional"))
      (node (ref "U$20") (pin "4") (pinfunction "Y_4") (pintype "bidirectional"))
    )
    (net (code "82") (name "Net-(U$21-1:GATE)") (class "Default")
      (node (ref "R39") (pin "1") (pinfunction "1_1") (pintype "bidirectional"))
      (node (ref "R40") (pin "1") (pinfunction "1_1") (pintype "bidirectional"))
      (node (ref "U$21") (pin "1") (pinfunction "1:GATE_1") (pintype "bidirectional"))
    )
    (net (code "83") (name "Net-(U$21-2:SOURCE)") (class "Default")
      (node (ref "R26") (pin "1") (pinfunction "1_1") (pintype "bidirectional"))
      (node (ref "U$21") (pin "2") (pinfunction "2:SOURCE_2") (pintype "bidirectional"))
      (node (ref "U$22") (pin "1") (pinfunction "1:GATE_1") (pintype "bidirectional"))
    )
    (net (code "84") (name "Net-(U$23-Y)") (class "Default")
      (node (ref "R32") (pin "1") (pinfunction "1_1") (pintype "bidirectional"))
      (node (ref "U$23") (pin "4") (pinfunction "Y_4") (pintype "bidirectional"))
    )
    (net (code "85") (name "Net-(U1-BS1)") (class "Default")
      (node (ref "R22") (pin "2") (pinfunction "2_2") (pintype "bidirectional"))
      (node (ref "U1") (pin "20") (pinfunction "BS1_20") (pintype "bidirectional"))
    )
    (net (code "86") (name "Net-(U1-C1N)") (class "Default")
      (node (ref "C4") (pin "1") (pinfunction "1_1") (pintype "passive"))
      (node (ref "U1") (pin "26") (pinfunction "C1N_26") (pintype "bidirectional"))
    )
    (net (code "87") (name "Net-(U1-C1P)") (class "Default")
      (node (ref "C4") (pin "2") (pinfunction "2_2") (pintype "passive"))
      (node (ref "U1") (pin "27") (pinfunction "C1P_27") (pintype "bidirectional"))
    )
    (net (code "88") (name "Net-(U1-C2N)") (class "Default")
      (node (ref "C5") (pin "1") (pinfunction "1_1") (pintype "passive"))
      (node (ref "U1") (pin "28") (pinfunction "C2N_28") (pintype "bidirectional"))
    )
    (net (code "89") (name "Net-(U1-C2P)") (class "Default")
      (node (ref "C5") (pin "2") (pinfunction "2_2") (pintype "passive"))
      (node (ref "U1") (pin "29") (pinfunction "C2P_29") (pintype "bidirectional"))
    )
    (net (code "90") (name "Net-(U1-IREF)") (class "Default")
      (node (ref "R35") (pin "1") (pinfunction "1_1") (pintype "bidirectional"))
      (node (ref "U1") (pin "5") (pinfunction "IREF_5") (pintype "bidirectional"))
    )
    (net (code "91") (name "Net-(U1-RES#)") (class "Default")
      (node (ref "R8") (pin "2") (pinfunction "2_2") (pintype "bidirectional"))
      (node (ref "U1") (pin "17") (pinfunction "RES#_17") (pintype "bidirectional"))
    )
    (net (code "92") (name "Net-(U1-VCC)") (class "Default")
      (node (ref "C8") (pin "2") (pinfunction "2_2") (pintype "passive"))
      (node (ref "U1") (pin "3") (pinfunction "VCC_3") (pintype "bidirectional"))
    )
    (net (code "93") (name "Net-(U1-VCOMH)") (class "Default")
      (node (ref "C9") (pin "2") (pinfunction "2_2") (pintype "passive"))
      (node (ref "U1") (pin "4") (pinfunction "VCOMH_4") (pintype "bidirectional"))
    )
    (net (code "94") (name "unconnected-(IC1-ADC6-Pad19)") (class "Default")
      (node (ref "IC1") (pin "19") (pinfunction "ADC6_19") (pintype "bidirectional"))
    )
    (net (code "95") (name "unconnected-(IC1-ADC7-Pad22)") (class "Default")
      (node (ref "IC1") (pin "22") (pinfunction "ADC7_22") (pintype "bidirectional"))
    )
    (net (code "96") (name "unconnected-(IC1-PB0(ICP)-Pad12)") (class "Default")
      (node (ref "IC1") (pin "12") (pinfunction "PB0(ICP)_12") (pintype "bidirectional"))
    )
    (net (code "97") (name "unconnected-(IC1-PB1(OC1A)-Pad13)") (class "Default")
      (node (ref "IC1") (pin "13") (pinfunction "PB1(OC1A)_13") (pintype "bidirectional"))
    )
    (net (code "98") (name "unconnected-(IC1-PB2(SS{slash}OC1B)-Pad14)") (class "Default")
      (node (ref "IC1") (pin "14") (pinfunction "PB2(SS/OC1B)_14") (pintype "bidirectional"))
    )
    (net (code "99") (name "unconnected-(IC1-PC2(ADC2)-Pad25)") (class "Default")
      (node (ref "IC1") (pin "25") (pinfunction "PC2(ADC2)_25") (pintype "bidirectional"))
    )
    (net (code "100") (name "unconnected-(IC1-PD5(T1)-Pad9)") (class "Default")
      (node (ref "IC1") (pin "9") (pinfunction "PD5(T1)_9") (pintype "bidirectional"))
    )
    (net (code "101") (name "unconnected-(IC1-PD6(AIN0)-Pad10)") (class "Default")
      (node (ref "IC1") (pin "10") (pinfunction "PD6(AIN0)_10") (pintype "bidirectional"))
    )
    (net (code "102") (name "unconnected-(IC1-PD7(AIN1)-Pad11)") (class "Default")
      (node (ref "IC1") (pin "11") (pinfunction "PD7(AIN1)_11") (pintype "bidirectional"))
    )
    (net (code "103") (name "unconnected-(IC2-CE1-Pad26)") (class "Default")
      (node (ref "IC2") (pin "26") (pinfunction "CE1_26") (pintype "bidirectional"))
    )
    (net (code "104") (name "unconnected-(IC2-ID_SC-Pad28)") (class "Default")
      (node (ref "IC2") (pin "28") (pinfunction "ID_SC_28") (pintype "bidirectional"))
    )
    (net (code "105") (name "unconnected-(IC2-ID_SD-Pad27)") (class "Default")
      (node (ref "IC2") (pin "27") (pinfunction "ID_SD_27") (pintype "bidirectional"))
    )
    (net (code "106") (name "unconnected-(IC3-A2-Pad11)") (class "Default")
      (node (ref "IC3") (pin "11") (pinfunction "A2_11") (pintype "bidirectional"))
    )
    (net (code "107") (name "unconnected-(IC3-A3-Pad14)") (class "Default")
      (node (ref "IC3") (pin "14") (pinfunction "A3_14") (pintype "bidirectional"))
    )
    (net (code "108") (name "unconnected-(IC3-B2-Pad10)") (class "Default")
      (node (ref "IC3") (pin "10") (pinfunction "B2_10") (pintype "bidirectional"))
    )
    (net (code "109") (name "unconnected-(IC3-B3-Pad13)") (class "Default")
      (node (ref "IC3") (pin "13") (pinfunction "B3_13") (pintype "bidirectional"))
    )
    (net (code "110") (name "unconnected-(IC3-Y2-Pad9)") (class "Default")
      (node (ref "IC3") (pin "9") (pinfunction "Y2_9") (pintype "bidirectional"))
    )
    (net (code "111") (name "unconnected-(IC3-Y3-Pad12)") (class "Default")
      (node (ref "IC3") (pin "12") (pinfunction "Y3_12") (pintype "bidirectional"))
    )
    (net (code "112") (name "unconnected-(IC4-LED2-Pad8)") (class "Default")
      (node (ref "IC4") (pin "8") (pinfunction "LED2_8") (pintype "bidirectional"))
    )
    (net (code "113") (name "unconnected-(IC4-LED3-Pad9)") (class "Default")
      (node (ref "IC4") (pin "9") (pinfunction "LED3_9") (pintype "bidirectional"))
    )
    (net (code "114") (name "unconnected-(IC4-LED4-Pad10)") (class "Default")
      (node (ref "IC4") (pin "10") (pinfunction "LED4_10") (pintype "bidirectional"))
    )
    (net (code "115") (name "unconnected-(IC4-LED5-Pad11)") (class "Default")
      (node (ref "IC4") (pin "11") (pinfunction "LED5_11") (pintype "bidirectional"))
    )
    (net (code "116") (name "unconnected-(IC4-LED6-Pad12)") (class "Default")
      (node (ref "IC4") (pin "12") (pinfunction "LED6_12") (pintype "bidirectional"))
    )
    (net (code "117") (name "unconnected-(IC4-LED7-Pad13)") (class "Default")
      (node (ref "IC4") (pin "13") (pinfunction "LED7_13") (pintype "bidirectional"))
    )
    (net (code "118") (name "unconnected-(IC4-LED8-Pad15)") (class "Default")
      (node (ref "IC4") (pin "15") (pinfunction "LED8_15") (pintype "bidirectional"))
    )
    (net (code "119") (name "unconnected-(IC4-LED9-Pad16)") (class "Default")
      (node (ref "IC4") (pin "16") (pinfunction "LED9_16") (pintype "bidirectional"))
    )
    (net (code "120") (name "unconnected-(IC4-LED10-Pad17)") (class "Default")
      (node (ref "IC4") (pin "17") (pinfunction "LED10_17") (pintype "bidirectional"))
    )
    (net (code "121") (name "unconnected-(IC4-LED11-Pad18)") (class "Default")
      (node (ref "IC4") (pin "18") (pinfunction "LED11_18") (pintype "bidirectional"))
    )
    (net (code "122") (name "unconnected-(IC4-LED12-Pad19)") (class "Default")
      (node (ref "IC4") (pin "19") (pinfunction "LED12_19") (pintype "bidirectional"))
    )
    (net (code "123") (name "unconnected-(IC4-LED13-Pad20)") (class "Default")
      (node (ref "IC4") (pin "20") (pinfunction "LED13_20") (pintype "bidirectional"))
    )
    (net (code "124") (name "unconnected-(IC4-LED14-Pad21)") (class "Default")
      (node (ref "IC4") (pin "21") (pinfunction "LED14_21") (pintype "bidirectional"))
    )
    (net (code "125") (name "unconnected-(IC4-LED15-Pad22)") (class "Default")
      (node (ref "IC4") (pin "22") (pinfunction "LED15_22") (pintype "bidirectional"))
    )
    (net (code "126") (name "unconnected-(U1-NC-Pad1)") (class "Default")
      (node (ref "U1") (pin "1") (pinfunction "NC_1") (pintype "bidirectional"))
    )
    (net (code "127") (name "unconnected-(U1-NC-Pad24)") (class "Default")
      (node (ref "U1") (pin "24") (pinfunction "NC_24") (pintype "bidirectional"))
    )
    (net (code "128") (name "unconnected-(U1-NC-Pad30)") (class "Default")
      (node (ref "U1") (pin "30") (pinfunction "NC_30") (pintype "bidirectional"))
    )
  )
)
